# PowerSupplies.net
KiCad netlist of a schematic drawn in Altium Designer
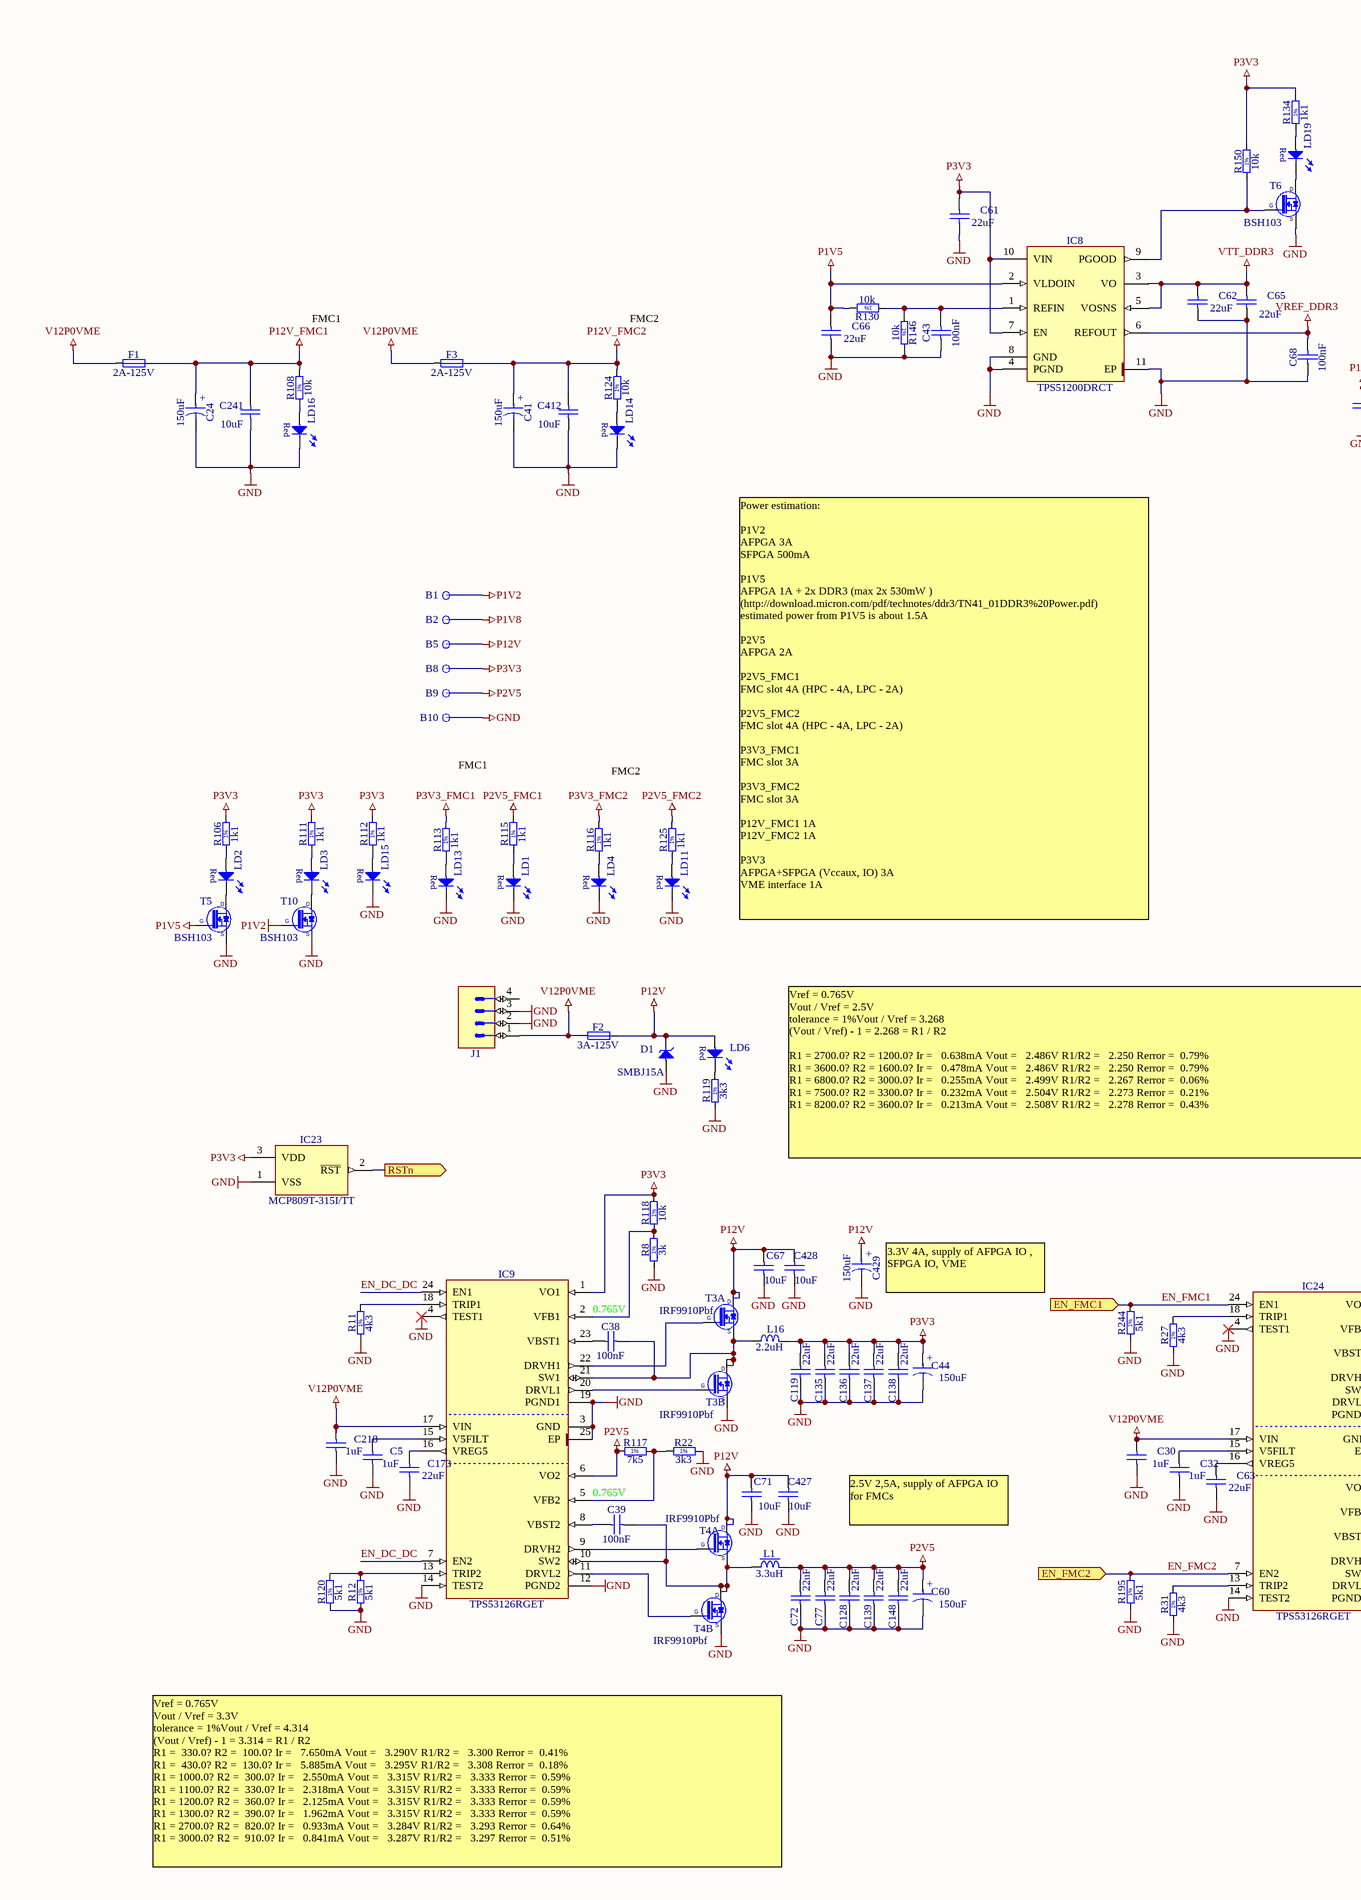
[diagram p0: PowerSupplies.SchDoc, left]
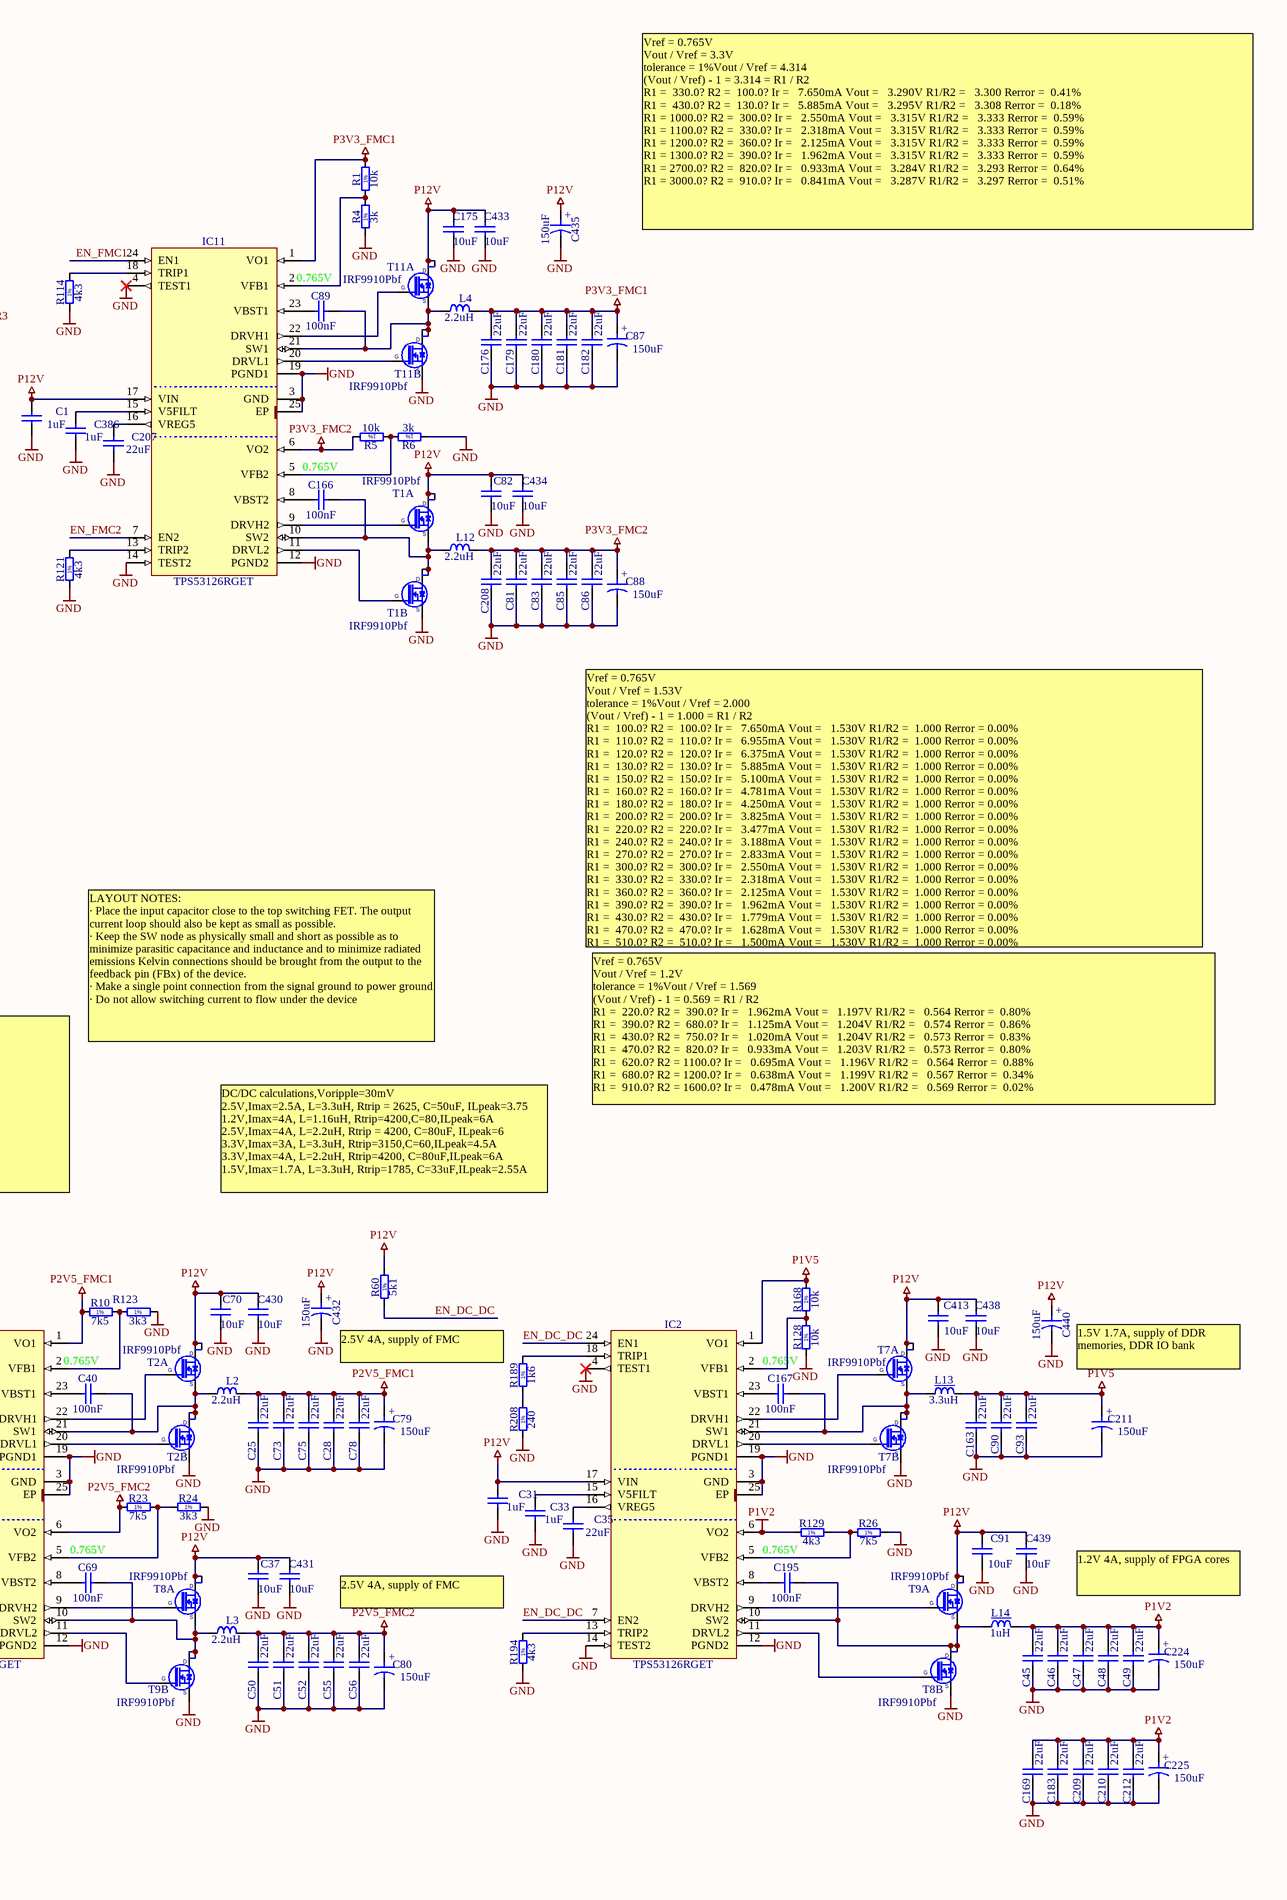
[diagram p1: PowerSupplies.SchDoc, right]

(export (version "E")
  (design (tool "Eeschema 10.0.6"))
  (components
    (comp (ref "B1")
      (value "Plated Hole")
      (footprint "c130h80")
      (description "Single Terminal Socket")
      (fields (field (name "PART NUMBER") "PLATED_HOLE0.8_PAD1.3") (field (name "AUTHOR") "CERN DEM JLC"))
      (libsource (lib "Eletro-mechanical") (part "Single Terminal Socket"))
    )
    (comp (ref "B2")
      (value "Plated Hole")
      (footprint "c130h80")
      (description "Single Terminal Socket")
      (fields (field (name "PART NUMBER") "PLATED_HOLE0.8_PAD1.3") (field (name "AUTHOR") "CERN DEM JLC"))
      (libsource (lib "Eletro-mechanical") (part "Single Terminal Socket"))
    )
    (comp (ref "B5")
      (value "Plated Hole")
      (footprint "c130h80")
      (description "Single Terminal Socket")
      (fields (field (name "PART NUMBER") "PLATED_HOLE0.8_PAD1.3") (field (name "AUTHOR") "CERN DEM JLC"))
      (libsource (lib "Eletro-mechanical") (part "Single Terminal Socket"))
    )
    (comp (ref "B8")
      (value "Plated Hole")
      (footprint "c130h80")
      (description "Single Terminal Socket")
      (fields (field (name "PART NUMBER") "PLATED_HOLE0.8_PAD1.3") (field (name "AUTHOR") "CERN DEM JLC"))
      (libsource (lib "Eletro-mechanical") (part "Single Terminal Socket"))
    )
    (comp (ref "B9")
      (value "Plated Hole")
      (footprint "c130h80")
      (description "Single Terminal Socket")
      (fields (field (name "PART NUMBER") "PLATED_HOLE0.8_PAD1.3") (field (name "AUTHOR") "CERN DEM JLC"))
      (libsource (lib "Eletro-mechanical") (part "Single Terminal Socket"))
    )
    (comp (ref "B10")
      (value "Plated Hole")
      (footprint "c130h80")
      (description "Single Terminal Socket")
      (fields (field (name "PART NUMBER") "PLATED_HOLE0.8_PAD1.3") (field (name "AUTHOR") "CERN DEM JLC"))
      (libsource (lib "Eletro-mechanical") (part "Single Terminal Socket"))
    )
    (comp (ref "C1")
      (value "1uF")
      (footprint "CAPC1608X87N")
      (description "Non-polarised capacitor")
      (fields
        (field (name "PART NUMBER") "CC0603_1UF_16V_10%_X7R")
        (field (name "VOLTAGE") "16V")
        (field (name "AUTHOR") "CERN DEM JLC")
      )
      (libsource (lib "Capacitors") (part "Capacitor - non polarized"))
    )
    (comp (ref "C5")
      (value "1uF")
      (footprint "CAPC1608X87N")
      (description "Non-polarised capacitor")
      (fields
        (field (name "PART NUMBER") "CC0603_1UF_16V_10%_X7R")
        (field (name "VOLTAGE") "16V")
        (field (name "AUTHOR") "CERN DEM JLC")
      )
      (libsource (lib "Capacitors") (part "Capacitor - non polarized"))
    )
    (comp (ref "C24")
      (value "150uF")
      (footprint "CAPPR350-850X700")
      (description "Polarised capacitor")
      (fields
        (field (name "PART NUMBER") "CAER_150UF_6.3V_20%_SANYO_6SEQP150M")
        (field (name "VOLTAGE") "6.3V")
        (field (name "AUTHOR") "CERN DEM JLC")
      )
      (libsource (lib "Capacitors") (part "Capacitor - polarized"))
    )
    (comp (ref "C25")
      (value "22uF")
      (footprint "CAPC3216X180N")
      (description "Non-polarised capacitor")
      (fields
        (field (name "PART NUMBER") "CC1206_22UF_10V_10%_X7R")
        (field (name "VOLTAGE") "10V")
        (field (name "AUTHOR") "CERN DEM JLC")
      )
      (libsource (lib "Capacitors") (part "Capacitor - non polarized"))
    )
    (comp (ref "C28")
      (value "22uF")
      (footprint "CAPC3216X180N")
      (description "Non-polarised capacitor")
      (fields
        (field (name "PART NUMBER") "CC1206_22UF_10V_10%_X7R")
        (field (name "VOLTAGE") "10V")
        (field (name "AUTHOR") "CERN DEM JLC")
      )
      (libsource (lib "Capacitors") (part "Capacitor - non polarized"))
    )
    (comp (ref "C30")
      (value "1uF")
      (footprint "CAPC1608X87N")
      (description "Non-polarised capacitor")
      (fields
        (field (name "PART NUMBER") "CC0603_1UF_16V_10%_X7R")
        (field (name "VOLTAGE") "16V")
        (field (name "AUTHOR") "CERN DEM JLC")
      )
      (libsource (lib "Capacitors") (part "Capacitor - non polarized"))
    )
    (comp (ref "C31")
      (value "1uF")
      (footprint "CAPC1608X87N")
      (description "Non-polarised capacitor")
      (fields
        (field (name "PART NUMBER") "CC0603_1UF_16V_10%_X7R")
        (field (name "VOLTAGE") "16V")
        (field (name "AUTHOR") "CERN DEM JLC")
      )
      (libsource (lib "Capacitors") (part "Capacitor - non polarized"))
    )
    (comp (ref "C32")
      (value "1uF")
      (footprint "CAPC1608X87N")
      (description "Non-polarised capacitor")
      (fields
        (field (name "PART NUMBER") "CC0603_1UF_16V_10%_X7R")
        (field (name "VOLTAGE") "16V")
        (field (name "AUTHOR") "CERN DEM JLC")
      )
      (libsource (lib "Capacitors") (part "Capacitor - non polarized"))
    )
    (comp (ref "C33")
      (value "1uF")
      (footprint "CAPC1608X87N")
      (description "Non-polarised capacitor")
      (fields
        (field (name "PART NUMBER") "CC0603_1UF_16V_10%_X7R")
        (field (name "VOLTAGE") "16V")
        (field (name "AUTHOR") "CERN DEM JLC")
      )
      (libsource (lib "Capacitors") (part "Capacitor - non polarized"))
    )
    (comp (ref "C35")
      (value "22uF")
      (footprint "CAPC3216X180N")
      (description "Non-polarised capacitor")
      (fields
        (field (name "PART NUMBER") "CC1206_22UF_10V_10%_X7R")
        (field (name "VOLTAGE") "10V")
        (field (name "AUTHOR") "CERN DEM JLC")
      )
      (libsource (lib "Capacitors") (part "Capacitor - non polarized"))
    )
    (comp (ref "C37")
      (value "10uF")
      (footprint "CAPC3225X270N")
      (description "Non-polarised capacitor")
      (fields
        (field (name "PART NUMBER") "CC1210_10UF_25V_10%_X7R")
        (field (name "VOLTAGE") "25V")
        (field (name "AUTHOR") "CERN DEM JLC")
      )
      (libsource (lib "Capacitors") (part "Capacitor - non polarized"))
    )
    (comp (ref "C38")
      (value "100nF")
      (footprint "CAPC1005X55N")
      (description "Non-polarised capacitor")
      (fields
        (field (name "PART NUMBER") "CC0402_100NF_16V_10%_X7R")
        (field (name "VOLTAGE") "16V")
        (field (name "AUTHOR") "CERN DEM JLC")
      )
      (libsource (lib "Capacitors") (part "Capacitor - non polarized"))
    )
    (comp (ref "C39")
      (value "100nF")
      (footprint "CAPC1005X55N")
      (description "Non-polarised capacitor")
      (fields
        (field (name "PART NUMBER") "CC0402_100NF_16V_10%_X7R")
        (field (name "VOLTAGE") "16V")
        (field (name "AUTHOR") "CERN DEM JLC")
      )
      (libsource (lib "Capacitors") (part "Capacitor - non polarized"))
    )
    (comp (ref "C40")
      (value "100nF")
      (footprint "CAPC1005X55N")
      (description "Non-polarised capacitor")
      (fields
        (field (name "PART NUMBER") "CC0402_100NF_16V_10%_X7R")
        (field (name "VOLTAGE") "16V")
        (field (name "AUTHOR") "CERN DEM JLC")
      )
      (libsource (lib "Capacitors") (part "Capacitor - non polarized"))
    )
    (comp (ref "C41")
      (value "150uF")
      (footprint "CAPPR350-850X700")
      (description "Polarised capacitor")
      (fields
        (field (name "PART NUMBER") "CAER_150UF_6.3V_20%_SANYO_6SEQP150M")
        (field (name "VOLTAGE") "6.3V")
        (field (name "AUTHOR") "CERN DEM JLC")
      )
      (libsource (lib "Capacitors") (part "Capacitor - polarized"))
    )
    (comp (ref "C43")
      (value "100nF")
      (footprint "CAPC1005X55N")
      (description "Non-polarised capacitor")
      (fields
        (field (name "PART NUMBER") "CC0402_100NF_16V_10%_X7R")
        (field (name "VOLTAGE") "16V")
        (field (name "AUTHOR") "CERN DEM JLC")
      )
      (libsource (lib "Capacitors") (part "Capacitor - non polarized"))
    )
    (comp (ref "C44")
      (value "150uF")
      (footprint "CAPPR350-850X700")
      (description "Polarised capacitor")
      (fields
        (field (name "PART NUMBER") "CAER_150UF_6.3V_20%_SANYO_6SEQP150M")
        (field (name "VOLTAGE") "6.3V")
        (field (name "AUTHOR") "CERN DEM JLC")
      )
      (libsource (lib "Capacitors") (part "Capacitor - polarized"))
    )
    (comp (ref "C45")
      (value "22uF")
      (footprint "CAPC3216X180N")
      (description "Non-polarised capacitor")
      (fields
        (field (name "PART NUMBER") "CC1206_22UF_10V_10%_X7R")
        (field (name "VOLTAGE") "10V")
        (field (name "AUTHOR") "CERN DEM JLC")
      )
      (libsource (lib "Capacitors") (part "Capacitor - non polarized"))
    )
    (comp (ref "C46")
      (value "22uF")
      (footprint "CAPC3216X180N")
      (description "Non-polarised capacitor")
      (fields
        (field (name "PART NUMBER") "CC1206_22UF_10V_10%_X7R")
        (field (name "VOLTAGE") "10V")
        (field (name "AUTHOR") "CERN DEM JLC")
      )
      (libsource (lib "Capacitors") (part "Capacitor - non polarized"))
    )
    (comp (ref "C47")
      (value "22uF")
      (footprint "CAPC3216X180N")
      (description "Non-polarised capacitor")
      (fields
        (field (name "PART NUMBER") "CC1206_22UF_10V_10%_X7R")
        (field (name "VOLTAGE") "10V")
        (field (name "AUTHOR") "CERN DEM JLC")
      )
      (libsource (lib "Capacitors") (part "Capacitor - non polarized"))
    )
    (comp (ref "C48")
      (value "22uF")
      (footprint "CAPC3216X180N")
      (description "Non-polarised capacitor")
      (fields
        (field (name "PART NUMBER") "CC1206_22UF_10V_10%_X7R")
        (field (name "VOLTAGE") "10V")
        (field (name "AUTHOR") "CERN DEM JLC")
      )
      (libsource (lib "Capacitors") (part "Capacitor - non polarized"))
    )
    (comp (ref "C49")
      (value "22uF")
      (footprint "CAPC3216X180N")
      (description "Non-polarised capacitor")
      (fields
        (field (name "PART NUMBER") "CC1206_22UF_10V_10%_X7R")
        (field (name "VOLTAGE") "10V")
        (field (name "AUTHOR") "CERN DEM JLC")
      )
      (libsource (lib "Capacitors") (part "Capacitor - non polarized"))
    )
    (comp (ref "C50")
      (value "22uF")
      (footprint "CAPC3216X180N")
      (description "Non-polarised capacitor")
      (fields
        (field (name "PART NUMBER") "CC1206_22UF_10V_10%_X7R")
        (field (name "VOLTAGE") "10V")
        (field (name "AUTHOR") "CERN DEM JLC")
      )
      (libsource (lib "Capacitors") (part "Capacitor - non polarized"))
    )
    (comp (ref "C51")
      (value "22uF")
      (footprint "CAPC3216X180N")
      (description "Non-polarised capacitor")
      (fields
        (field (name "PART NUMBER") "CC1206_22UF_10V_10%_X7R")
        (field (name "VOLTAGE") "10V")
        (field (name "AUTHOR") "CERN DEM JLC")
      )
      (libsource (lib "Capacitors") (part "Capacitor - non polarized"))
    )
    (comp (ref "C52")
      (value "22uF")
      (footprint "CAPC3216X180N")
      (description "Non-polarised capacitor")
      (fields
        (field (name "PART NUMBER") "CC1206_22UF_10V_10%_X7R")
        (field (name "VOLTAGE") "10V")
        (field (name "AUTHOR") "CERN DEM JLC")
      )
      (libsource (lib "Capacitors") (part "Capacitor - non polarized"))
    )
    (comp (ref "C55")
      (value "22uF")
      (footprint "CAPC3216X180N")
      (description "Non-polarised capacitor")
      (fields
        (field (name "PART NUMBER") "CC1206_22UF_10V_10%_X7R")
        (field (name "VOLTAGE") "10V")
        (field (name "AUTHOR") "CERN DEM JLC")
      )
      (libsource (lib "Capacitors") (part "Capacitor - non polarized"))
    )
    (comp (ref "C56")
      (value "22uF")
      (footprint "CAPC3216X180N")
      (description "Non-polarised capacitor")
      (fields
        (field (name "PART NUMBER") "CC1206_22UF_10V_10%_X7R")
        (field (name "VOLTAGE") "10V")
        (field (name "AUTHOR") "CERN DEM JLC")
      )
      (libsource (lib "Capacitors") (part "Capacitor - non polarized"))
    )
    (comp (ref "C60")
      (value "150uF")
      (footprint "CAPPR350-850X700")
      (description "Polarised capacitor")
      (fields
        (field (name "PART NUMBER") "CAER_150UF_6.3V_20%_SANYO_6SEQP150M")
        (field (name "VOLTAGE") "6.3V")
        (field (name "AUTHOR") "CERN DEM JLC")
      )
      (libsource (lib "Capacitors") (part "Capacitor - polarized"))
    )
    (comp (ref "C61")
      (value "22uF")
      (footprint "CAPC3216X180N")
      (description "Non-polarised capacitor")
      (fields
        (field (name "PART NUMBER") "CC1206_22UF_10V_10%_X7R")
        (field (name "VOLTAGE") "10V")
        (field (name "AUTHOR") "CERN DEM JLC")
      )
      (libsource (lib "Capacitors") (part "Capacitor - non polarized"))
    )
    (comp (ref "C62")
      (value "22uF")
      (footprint "CAPC3216X180N")
      (description "Non-polarised capacitor")
      (fields
        (field (name "PART NUMBER") "CC1206_22UF_10V_10%_X7R")
        (field (name "VOLTAGE") "10V")
        (field (name "AUTHOR") "CERN DEM JLC")
      )
      (libsource (lib "Capacitors") (part "Capacitor - non polarized"))
    )
    (comp (ref "C63")
      (value "22uF")
      (footprint "CAPC3216X180N")
      (description "Non-polarised capacitor")
      (fields
        (field (name "PART NUMBER") "CC1206_22UF_10V_10%_X7R")
        (field (name "VOLTAGE") "10V")
        (field (name "AUTHOR") "CERN DEM JLC")
      )
      (libsource (lib "Capacitors") (part "Capacitor - non polarized"))
    )
    (comp (ref "C65")
      (value "22uF")
      (footprint "CAPC3216X180N")
      (description "Non-polarised capacitor")
      (fields
        (field (name "PART NUMBER") "CC1206_22UF_10V_10%_X7R")
        (field (name "VOLTAGE") "10V")
        (field (name "AUTHOR") "CERN DEM JLC")
      )
      (libsource (lib "Capacitors") (part "Capacitor - non polarized"))
    )
    (comp (ref "C66")
      (value "22uF")
      (footprint "CAPC3216X180N")
      (description "Non-polarised capacitor")
      (fields
        (field (name "PART NUMBER") "CC1206_22UF_10V_10%_X7R")
        (field (name "VOLTAGE") "10V")
        (field (name "AUTHOR") "CERN DEM JLC")
      )
      (libsource (lib "Capacitors") (part "Capacitor - non polarized"))
    )
    (comp (ref "C67")
      (value "10uF")
      (footprint "CAPC3225X270N")
      (description "Non-polarised capacitor")
      (fields
        (field (name "PART NUMBER") "CC1210_10UF_25V_10%_X7R")
        (field (name "VOLTAGE") "25V")
        (field (name "AUTHOR") "CERN DEM JLC")
      )
      (libsource (lib "Capacitors") (part "Capacitor - non polarized"))
    )
    (comp (ref "C68")
      (value "100nF")
      (footprint "CAPC1005X55N")
      (description "Non-polarised capacitor")
      (fields
        (field (name "PART NUMBER") "CC0402_100NF_16V_10%_X7R")
        (field (name "VOLTAGE") "16V")
        (field (name "AUTHOR") "CERN DEM JLC")
      )
      (libsource (lib "Capacitors") (part "Capacitor - non polarized"))
    )
    (comp (ref "C69")
      (value "100nF")
      (footprint "CAPC1005X55N")
      (description "Non-polarised capacitor")
      (fields
        (field (name "PART NUMBER") "CC0402_100NF_16V_10%_X7R")
        (field (name "VOLTAGE") "16V")
        (field (name "AUTHOR") "CERN DEM JLC")
      )
      (libsource (lib "Capacitors") (part "Capacitor - non polarized"))
    )
    (comp (ref "C70")
      (value "10uF")
      (footprint "CAPC3225X270N")
      (description "Non-polarised capacitor")
      (fields
        (field (name "PART NUMBER") "CC1210_10UF_25V_10%_X7R")
        (field (name "VOLTAGE") "25V")
        (field (name "AUTHOR") "CERN DEM JLC")
      )
      (libsource (lib "Capacitors") (part "Capacitor - non polarized"))
    )
    (comp (ref "C71")
      (value "10uF")
      (footprint "CAPC3225X270N")
      (description "Non-polarised capacitor")
      (fields
        (field (name "PART NUMBER") "CC1210_10UF_25V_10%_X7R")
        (field (name "VOLTAGE") "25V")
        (field (name "AUTHOR") "CERN DEM JLC")
      )
      (libsource (lib "Capacitors") (part "Capacitor - non polarized"))
    )
    (comp (ref "C72")
      (value "22uF")
      (footprint "CAPC3216X180N")
      (description "Non-polarised capacitor")
      (fields
        (field (name "PART NUMBER") "CC1206_22UF_10V_10%_X7R")
        (field (name "VOLTAGE") "10V")
        (field (name "AUTHOR") "CERN DEM JLC")
      )
      (libsource (lib "Capacitors") (part "Capacitor - non polarized"))
    )
    (comp (ref "C73")
      (value "22uF")
      (footprint "CAPC3216X180N")
      (description "Non-polarised capacitor")
      (fields
        (field (name "PART NUMBER") "CC1206_22UF_10V_10%_X7R")
        (field (name "VOLTAGE") "10V")
        (field (name "AUTHOR") "CERN DEM JLC")
      )
      (libsource (lib "Capacitors") (part "Capacitor - non polarized"))
    )
    (comp (ref "C75")
      (value "22uF")
      (footprint "CAPC3216X180N")
      (description "Non-polarised capacitor")
      (fields
        (field (name "PART NUMBER") "CC1206_22UF_10V_10%_X7R")
        (field (name "VOLTAGE") "10V")
        (field (name "AUTHOR") "CERN DEM JLC")
      )
      (libsource (lib "Capacitors") (part "Capacitor - non polarized"))
    )
    (comp (ref "C77")
      (value "22uF")
      (footprint "CAPC3216X180N")
      (description "Non-polarised capacitor")
      (fields
        (field (name "PART NUMBER") "CC1206_22UF_10V_10%_X7R")
        (field (name "VOLTAGE") "10V")
        (field (name "AUTHOR") "CERN DEM JLC")
      )
      (libsource (lib "Capacitors") (part "Capacitor - non polarized"))
    )
    (comp (ref "C78")
      (value "22uF")
      (footprint "CAPC3216X180N")
      (description "Non-polarised capacitor")
      (fields
        (field (name "PART NUMBER") "CC1206_22UF_10V_10%_X7R")
        (field (name "VOLTAGE") "10V")
        (field (name "AUTHOR") "CERN DEM JLC")
      )
      (libsource (lib "Capacitors") (part "Capacitor - non polarized"))
    )
    (comp (ref "C79")
      (value "150uF")
      (footprint "CAPPR350-850X700")
      (description "Polarised capacitor")
      (fields
        (field (name "PART NUMBER") "CAER_150UF_6.3V_20%_SANYO_6SEQP150M")
        (field (name "VOLTAGE") "6.3V")
        (field (name "AUTHOR") "CERN DEM JLC")
      )
      (libsource (lib "Capacitors") (part "Capacitor - polarized"))
    )
    (comp (ref "C80")
      (value "150uF")
      (footprint "CAPPR350-850X700")
      (description "Polarised capacitor")
      (fields
        (field (name "PART NUMBER") "CAER_150UF_6.3V_20%_SANYO_6SEQP150M")
        (field (name "VOLTAGE") "6.3V")
        (field (name "AUTHOR") "CERN DEM JLC")
      )
      (libsource (lib "Capacitors") (part "Capacitor - polarized"))
    )
    (comp (ref "C81")
      (value "22uF")
      (footprint "CAPC3216X180N")
      (description "Non-polarised capacitor")
      (fields
        (field (name "PART NUMBER") "CC1206_22UF_10V_10%_X7R")
        (field (name "VOLTAGE") "10V")
        (field (name "AUTHOR") "CERN DEM JLC")
      )
      (libsource (lib "Capacitors") (part "Capacitor - non polarized"))
    )
    (comp (ref "C82")
      (value "10uF")
      (footprint "CAPC3225X270N")
      (description "Non-polarised capacitor")
      (fields
        (field (name "PART NUMBER") "CC1210_10UF_25V_10%_X7R")
        (field (name "VOLTAGE") "25V")
        (field (name "AUTHOR") "CERN DEM JLC")
      )
      (libsource (lib "Capacitors") (part "Capacitor - non polarized"))
    )
    (comp (ref "C83")
      (value "22uF")
      (footprint "CAPC3216X180N")
      (description "Non-polarised capacitor")
      (fields
        (field (name "PART NUMBER") "CC1206_22UF_10V_10%_X7R")
        (field (name "VOLTAGE") "10V")
        (field (name "AUTHOR") "CERN DEM JLC")
      )
      (libsource (lib "Capacitors") (part "Capacitor - non polarized"))
    )
    (comp (ref "C85")
      (value "22uF")
      (footprint "CAPC3216X180N")
      (description "Non-polarised capacitor")
      (fields
        (field (name "PART NUMBER") "CC1206_22UF_10V_10%_X7R")
        (field (name "VOLTAGE") "10V")
        (field (name "AUTHOR") "CERN DEM JLC")
      )
      (libsource (lib "Capacitors") (part "Capacitor - non polarized"))
    )
    (comp (ref "C86")
      (value "22uF")
      (footprint "CAPC3216X180N")
      (description "Non-polarised capacitor")
      (fields
        (field (name "PART NUMBER") "CC1206_22UF_10V_10%_X7R")
        (field (name "VOLTAGE") "10V")
        (field (name "AUTHOR") "CERN DEM JLC")
      )
      (libsource (lib "Capacitors") (part "Capacitor - non polarized"))
    )
    (comp (ref "C87")
      (value "150uF")
      (footprint "CAPPR350-850X700")
      (description "Polarised capacitor")
      (fields
        (field (name "PART NUMBER") "CAER_150UF_6.3V_20%_SANYO_6SEQP150M")
        (field (name "VOLTAGE") "6.3V")
        (field (name "AUTHOR") "CERN DEM JLC")
      )
      (libsource (lib "Capacitors") (part "Capacitor - polarized"))
    )
    (comp (ref "C88")
      (value "150uF")
      (footprint "CAPPR350-850X700")
      (description "Polarised capacitor")
      (fields
        (field (name "PART NUMBER") "CAER_150UF_6.3V_20%_SANYO_6SEQP150M")
        (field (name "VOLTAGE") "6.3V")
        (field (name "AUTHOR") "CERN DEM JLC")
      )
      (libsource (lib "Capacitors") (part "Capacitor - polarized"))
    )
    (comp (ref "C89")
      (value "100nF")
      (footprint "CAPC1005X55N")
      (description "Non-polarised capacitor")
      (fields
        (field (name "PART NUMBER") "CC0402_100NF_16V_10%_X7R")
        (field (name "VOLTAGE") "16V")
        (field (name "AUTHOR") "CERN DEM JLC")
      )
      (libsource (lib "Capacitors") (part "Capacitor - non polarized"))
    )
    (comp (ref "C90")
      (value "22uF")
      (footprint "CAPC3216X180N")
      (description "Non-polarised capacitor")
      (fields
        (field (name "PART NUMBER") "CC1206_22UF_10V_10%_X7R")
        (field (name "VOLTAGE") "10V")
        (field (name "AUTHOR") "CERN DEM JLC")
      )
      (libsource (lib "Capacitors") (part "Capacitor - non polarized"))
    )
    (comp (ref "C91")
      (value "10uF")
      (footprint "CAPC3225X270N")
      (description "Non-polarised capacitor")
      (fields
        (field (name "PART NUMBER") "CC1210_10UF_25V_10%_X7R")
        (field (name "VOLTAGE") "25V")
        (field (name "AUTHOR") "CERN DEM JLC")
      )
      (libsource (lib "Capacitors") (part "Capacitor - non polarized"))
    )
    (comp (ref "C93")
      (value "22uF")
      (footprint "CAPC3216X180N")
      (description "Non-polarised capacitor")
      (fields
        (field (name "PART NUMBER") "CC1206_22UF_10V_10%_X7R")
        (field (name "VOLTAGE") "10V")
        (field (name "AUTHOR") "CERN DEM JLC")
      )
      (libsource (lib "Capacitors") (part "Capacitor - non polarized"))
    )
    (comp (ref "C119")
      (value "22uF")
      (footprint "CAPC3216X180N")
      (description "Non-polarised capacitor")
      (fields
        (field (name "PART NUMBER") "CC1206_22UF_10V_10%_X7R")
        (field (name "VOLTAGE") "10V")
        (field (name "AUTHOR") "CERN DEM JLC")
      )
      (libsource (lib "Capacitors") (part "Capacitor - non polarized"))
    )
    (comp (ref "C128")
      (value "22uF")
      (footprint "CAPC3216X180N")
      (description "Non-polarised capacitor")
      (fields
        (field (name "PART NUMBER") "CC1206_22UF_10V_10%_X7R")
        (field (name "VOLTAGE") "10V")
        (field (name "AUTHOR") "CERN DEM JLC")
      )
      (libsource (lib "Capacitors") (part "Capacitor - non polarized"))
    )
    (comp (ref "C135")
      (value "22uF")
      (footprint "CAPC3216X180N")
      (description "Non-polarised capacitor")
      (fields
        (field (name "PART NUMBER") "CC1206_22UF_10V_10%_X7R")
        (field (name "VOLTAGE") "10V")
        (field (name "AUTHOR") "CERN DEM JLC")
      )
      (libsource (lib "Capacitors") (part "Capacitor - non polarized"))
    )
    (comp (ref "C136")
      (value "22uF")
      (footprint "CAPC3216X180N")
      (description "Non-polarised capacitor")
      (fields
        (field (name "PART NUMBER") "CC1206_22UF_10V_10%_X7R")
        (field (name "VOLTAGE") "10V")
        (field (name "AUTHOR") "CERN DEM JLC")
      )
      (libsource (lib "Capacitors") (part "Capacitor - non polarized"))
    )
    (comp (ref "C137")
      (value "22uF")
      (footprint "CAPC3216X180N")
      (description "Non-polarised capacitor")
      (fields
        (field (name "PART NUMBER") "CC1206_22UF_10V_10%_X7R")
        (field (name "VOLTAGE") "10V")
        (field (name "AUTHOR") "CERN DEM JLC")
      )
      (libsource (lib "Capacitors") (part "Capacitor - non polarized"))
    )
    (comp (ref "C138")
      (value "22uF")
      (footprint "CAPC3216X180N")
      (description "Non-polarised capacitor")
      (fields
        (field (name "PART NUMBER") "CC1206_22UF_10V_10%_X7R")
        (field (name "VOLTAGE") "10V")
        (field (name "AUTHOR") "CERN DEM JLC")
      )
      (libsource (lib "Capacitors") (part "Capacitor - non polarized"))
    )
    (comp (ref "C139")
      (value "22uF")
      (footprint "CAPC3216X180N")
      (description "Non-polarised capacitor")
      (fields
        (field (name "PART NUMBER") "CC1206_22UF_10V_10%_X7R")
        (field (name "VOLTAGE") "10V")
        (field (name "AUTHOR") "CERN DEM JLC")
      )
      (libsource (lib "Capacitors") (part "Capacitor - non polarized"))
    )
    (comp (ref "C148")
      (value "22uF")
      (footprint "CAPC3216X180N")
      (description "Non-polarised capacitor")
      (fields
        (field (name "PART NUMBER") "CC1206_22UF_10V_10%_X7R")
        (field (name "VOLTAGE") "10V")
        (field (name "AUTHOR") "CERN DEM JLC")
      )
      (libsource (lib "Capacitors") (part "Capacitor - non polarized"))
    )
    (comp (ref "C163")
      (value "22uF")
      (footprint "CAPC3216X180N")
      (description "Non-polarised capacitor")
      (fields
        (field (name "PART NUMBER") "CC1206_22UF_10V_10%_X7R")
        (field (name "VOLTAGE") "10V")
        (field (name "AUTHOR") "CERN DEM JLC")
      )
      (libsource (lib "Capacitors") (part "Capacitor - non polarized"))
    )
    (comp (ref "C166")
      (value "100nF")
      (footprint "CAPC1005X55N")
      (description "Non-polarised capacitor")
      (fields
        (field (name "PART NUMBER") "CC0402_100NF_16V_10%_X7R")
        (field (name "VOLTAGE") "16V")
        (field (name "AUTHOR") "CERN DEM JLC")
      )
      (libsource (lib "Capacitors") (part "Capacitor - non polarized"))
    )
    (comp (ref "C167")
      (value "100nF")
      (footprint "CAPC1005X55N")
      (description "Non-polarised capacitor")
      (fields
        (field (name "PART NUMBER") "CC0402_100NF_16V_10%_X7R")
        (field (name "VOLTAGE") "16V")
        (field (name "AUTHOR") "CERN DEM JLC")
      )
      (libsource (lib "Capacitors") (part "Capacitor - non polarized"))
    )
    (comp (ref "C169")
      (value "22uF")
      (footprint "CAPC3216X180N")
      (description "Non-polarised capacitor")
      (fields
        (field (name "PART NUMBER") "CC1206_22UF_10V_10%_X7R")
        (field (name "VOLTAGE") "10V")
        (field (name "AUTHOR") "CERN DEM JLC")
      )
      (libsource (lib "Capacitors") (part "Capacitor - non polarized"))
    )
    (comp (ref "C173")
      (value "22uF")
      (footprint "CAPC3216X180N")
      (description "Non-polarised capacitor")
      (fields
        (field (name "PART NUMBER") "CC1206_22UF_10V_10%_X7R")
        (field (name "VOLTAGE") "10V")
        (field (name "AUTHOR") "CERN DEM JLC")
      )
      (libsource (lib "Capacitors") (part "Capacitor - non polarized"))
    )
    (comp (ref "C175")
      (value "10uF")
      (footprint "CAPC3225X270N")
      (description "Non-polarised capacitor")
      (fields
        (field (name "PART NUMBER") "CC1210_10UF_25V_10%_X7R")
        (field (name "VOLTAGE") "25V")
        (field (name "AUTHOR") "CERN DEM JLC")
      )
      (libsource (lib "Capacitors") (part "Capacitor - non polarized"))
    )
    (comp (ref "C176")
      (value "22uF")
      (footprint "CAPC3216X180N")
      (description "Non-polarised capacitor")
      (fields
        (field (name "PART NUMBER") "CC1206_22UF_10V_10%_X7R")
        (field (name "VOLTAGE") "10V")
        (field (name "AUTHOR") "CERN DEM JLC")
      )
      (libsource (lib "Capacitors") (part "Capacitor - non polarized"))
    )
    (comp (ref "C179")
      (value "22uF")
      (footprint "CAPC3216X180N")
      (description "Non-polarised capacitor")
      (fields
        (field (name "PART NUMBER") "CC1206_22UF_10V_10%_X7R")
        (field (name "VOLTAGE") "10V")
        (field (name "AUTHOR") "CERN DEM JLC")
      )
      (libsource (lib "Capacitors") (part "Capacitor - non polarized"))
    )
    (comp (ref "C180")
      (value "22uF")
      (footprint "CAPC3216X180N")
      (description "Non-polarised capacitor")
      (fields
        (field (name "PART NUMBER") "CC1206_22UF_10V_10%_X7R")
        (field (name "VOLTAGE") "10V")
        (field (name "AUTHOR") "CERN DEM JLC")
      )
      (libsource (lib "Capacitors") (part "Capacitor - non polarized"))
    )
    (comp (ref "C181")
      (value "22uF")
      (footprint "CAPC3216X180N")
      (description "Non-polarised capacitor")
      (fields
        (field (name "PART NUMBER") "CC1206_22UF_10V_10%_X7R")
        (field (name "VOLTAGE") "10V")
        (field (name "AUTHOR") "CERN DEM JLC")
      )
      (libsource (lib "Capacitors") (part "Capacitor - non polarized"))
    )
    (comp (ref "C182")
      (value "22uF")
      (footprint "CAPC3216X180N")
      (description "Non-polarised capacitor")
      (fields
        (field (name "PART NUMBER") "CC1206_22UF_10V_10%_X7R")
        (field (name "VOLTAGE") "10V")
        (field (name "AUTHOR") "CERN DEM JLC")
      )
      (libsource (lib "Capacitors") (part "Capacitor - non polarized"))
    )
    (comp (ref "C183")
      (value "22uF")
      (footprint "CAPC3216X180N")
      (description "Non-polarised capacitor")
      (fields
        (field (name "PART NUMBER") "CC1206_22UF_10V_10%_X7R")
        (field (name "VOLTAGE") "10V")
        (field (name "AUTHOR") "CERN DEM JLC")
      )
      (libsource (lib "Capacitors") (part "Capacitor - non polarized"))
    )
    (comp (ref "C195")
      (value "100nF")
      (footprint "CAPC1005X55N")
      (description "Non-polarised capacitor")
      (fields
        (field (name "PART NUMBER") "CC0402_100NF_16V_10%_X7R")
        (field (name "VOLTAGE") "16V")
        (field (name "AUTHOR") "CERN DEM JLC")
      )
      (libsource (lib "Capacitors") (part "Capacitor - non polarized"))
    )
    (comp (ref "C207")
      (value "22uF")
      (footprint "CAPC3216X180N")
      (description "Non-polarised capacitor")
      (fields
        (field (name "PART NUMBER") "CC1206_22UF_10V_10%_X7R")
        (field (name "VOLTAGE") "10V")
        (field (name "AUTHOR") "CERN DEM JLC")
      )
      (libsource (lib "Capacitors") (part "Capacitor - non polarized"))
    )
    (comp (ref "C208")
      (value "22uF")
      (footprint "CAPC3216X180N")
      (description "Non-polarised capacitor")
      (fields
        (field (name "PART NUMBER") "CC1206_22UF_10V_10%_X7R")
        (field (name "VOLTAGE") "10V")
        (field (name "AUTHOR") "CERN DEM JLC")
      )
      (libsource (lib "Capacitors") (part "Capacitor - non polarized"))
    )
    (comp (ref "C209")
      (value "22uF")
      (footprint "CAPC3216X180N")
      (description "Non-polarised capacitor")
      (fields
        (field (name "PART NUMBER") "CC1206_22UF_10V_10%_X7R")
        (field (name "VOLTAGE") "10V")
        (field (name "AUTHOR") "CERN DEM JLC")
      )
      (libsource (lib "Capacitors") (part "Capacitor - non polarized"))
    )
    (comp (ref "C210")
      (value "22uF")
      (footprint "CAPC3216X180N")
      (description "Non-polarised capacitor")
      (fields
        (field (name "PART NUMBER") "CC1206_22UF_10V_10%_X7R")
        (field (name "VOLTAGE") "10V")
        (field (name "AUTHOR") "CERN DEM JLC")
      )
      (libsource (lib "Capacitors") (part "Capacitor - non polarized"))
    )
    (comp (ref "C211")
      (value "150uF")
      (footprint "CAPPR350-850X700")
      (description "Polarised capacitor")
      (fields
        (field (name "PART NUMBER") "CAER_150UF_6.3V_20%_SANYO_6SEQP150M")
        (field (name "VOLTAGE") "6.3V")
        (field (name "AUTHOR") "CERN DEM JLC")
      )
      (libsource (lib "Capacitors") (part "Capacitor - polarized"))
    )
    (comp (ref "C212")
      (value "22uF")
      (footprint "CAPC3216X180N")
      (description "Non-polarised capacitor")
      (fields
        (field (name "PART NUMBER") "CC1206_22UF_10V_10%_X7R")
        (field (name "VOLTAGE") "10V")
        (field (name "AUTHOR") "CERN DEM JLC")
      )
      (libsource (lib "Capacitors") (part "Capacitor - non polarized"))
    )
    (comp (ref "C218")
      (value "1uF")
      (footprint "CAPC1608X87N")
      (description "Non-polarised capacitor")
      (fields
        (field (name "PART NUMBER") "CC0603_1UF_16V_10%_X7R")
        (field (name "VOLTAGE") "16V")
        (field (name "AUTHOR") "CERN DEM JLC")
      )
      (libsource (lib "Capacitors") (part "Capacitor - non polarized"))
    )
    (comp (ref "C224")
      (value "150uF")
      (footprint "CAPPR350-850X700")
      (description "Polarised capacitor")
      (fields
        (field (name "PART NUMBER") "CAER_150UF_6.3V_20%_SANYO_6SEQP150M")
        (field (name "VOLTAGE") "6.3V")
        (field (name "AUTHOR") "CERN DEM JLC")
      )
      (libsource (lib "Capacitors") (part "Capacitor - polarized"))
    )
    (comp (ref "C225")
      (value "150uF")
      (footprint "CAPPR350-850X700")
      (description "Polarised capacitor")
      (fields
        (field (name "PART NUMBER") "CAER_150UF_6.3V_20%_SANYO_6SEQP150M")
        (field (name "VOLTAGE") "6.3V")
        (field (name "AUTHOR") "CERN DEM JLC")
      )
      (libsource (lib "Capacitors") (part "Capacitor - polarized"))
    )
    (comp (ref "C241")
      (value "10uF")
      (footprint "CAPC3225X270N")
      (description "Non-polarised capacitor")
      (fields
        (field (name "PART NUMBER") "CC1210_10UF_25V_10%_X7R")
        (field (name "VOLTAGE") "25V")
        (field (name "AUTHOR") "CERN DEM JLC")
      )
      (libsource (lib "Capacitors") (part "Capacitor - non polarized"))
    )
    (comp (ref "C386")
      (value "1uF")
      (footprint "CAPC1608X87N")
      (description "Non-polarised capacitor")
      (fields
        (field (name "PART NUMBER") "CC0603_1UF_16V_10%_X7R")
        (field (name "VOLTAGE") "16V")
        (field (name "AUTHOR") "CERN DEM JLC")
      )
      (libsource (lib "Capacitors") (part "Capacitor - non polarized"))
    )
    (comp (ref "C412")
      (value "10uF")
      (footprint "CAPC3225X270N")
      (description "Non-polarised capacitor")
      (fields
        (field (name "PART NUMBER") "CC1210_10UF_25V_10%_X7R")
        (field (name "VOLTAGE") "25V")
        (field (name "AUTHOR") "CERN DEM JLC")
      )
      (libsource (lib "Capacitors") (part "Capacitor - non polarized"))
    )
    (comp (ref "C413")
      (value "10uF")
      (footprint "CAPC3225X270N")
      (description "Non-polarised capacitor")
      (fields
        (field (name "PART NUMBER") "CC1210_10UF_25V_10%_X7R")
        (field (name "VOLTAGE") "25V")
        (field (name "AUTHOR") "CERN DEM JLC")
      )
      (libsource (lib "Capacitors") (part "Capacitor - non polarized"))
    )
    (comp (ref "C427")
      (value "10uF")
      (footprint "CAPC3225X270N")
      (description "Non-polarised capacitor")
      (fields
        (field (name "PART NUMBER") "CC1210_10UF_25V_10%_X7R")
        (field (name "VOLTAGE") "25V")
        (field (name "AUTHOR") "CERN DEM JLC")
      )
      (libsource (lib "Capacitors") (part "Capacitor - non polarized"))
    )
    (comp (ref "C428")
      (value "10uF")
      (footprint "CAPC3225X270N")
      (description "Non-polarised capacitor")
      (fields
        (field (name "PART NUMBER") "CC1210_10UF_25V_10%_X7R")
        (field (name "VOLTAGE") "25V")
        (field (name "AUTHOR") "CERN DEM JLC")
      )
      (libsource (lib "Capacitors") (part "Capacitor - non polarized"))
    )
    (comp (ref "C429")
      (value "150uF")
      (footprint "CAPPR500-1050X800")
      (description "Polarised capacitor")
      (fields
        (field (name "PART NUMBER") "CAER_150UF_16V_20%_SANYO_16SEQP150M")
        (field (name "VOLTAGE") "16V")
        (field (name "AUTHOR") "CERN DEM JLC")
      )
      (libsource (lib "Capacitors") (part "Capacitor - polarized"))
    )
    (comp (ref "C430")
      (value "10uF")
      (footprint "CAPC3225X270N")
      (description "Non-polarised capacitor")
      (fields
        (field (name "PART NUMBER") "CC1210_10UF_25V_10%_X7R")
        (field (name "VOLTAGE") "25V")
        (field (name "AUTHOR") "CERN DEM JLC")
      )
      (libsource (lib "Capacitors") (part "Capacitor - non polarized"))
    )
    (comp (ref "C431")
      (value "10uF")
      (footprint "CAPC3225X270N")
      (description "Non-polarised capacitor")
      (fields
        (field (name "PART NUMBER") "CC1210_10UF_25V_10%_X7R")
        (field (name "VOLTAGE") "25V")
        (field (name "AUTHOR") "CERN DEM JLC")
      )
      (libsource (lib "Capacitors") (part "Capacitor - non polarized"))
    )
    (comp (ref "C432")
      (value "150uF")
      (footprint "CAPPR500-1050X800")
      (description "Polarised capacitor")
      (fields
        (field (name "PART NUMBER") "CAER_150UF_16V_20%_SANYO_16SEQP150M")
        (field (name "VOLTAGE") "16V")
        (field (name "AUTHOR") "CERN DEM JLC")
      )
      (libsource (lib "Capacitors") (part "Capacitor - polarized"))
    )
    (comp (ref "C433")
      (value "10uF")
      (footprint "CAPC3225X270N")
      (description "Non-polarised capacitor")
      (fields
        (field (name "PART NUMBER") "CC1210_10UF_25V_10%_X7R")
        (field (name "VOLTAGE") "25V")
        (field (name "AUTHOR") "CERN DEM JLC")
      )
      (libsource (lib "Capacitors") (part "Capacitor - non polarized"))
    )
    (comp (ref "C434")
      (value "10uF")
      (footprint "CAPC3225X270N")
      (description "Non-polarised capacitor")
      (fields
        (field (name "PART NUMBER") "CC1210_10UF_25V_10%_X7R")
        (field (name "VOLTAGE") "25V")
        (field (name "AUTHOR") "CERN DEM JLC")
      )
      (libsource (lib "Capacitors") (part "Capacitor - non polarized"))
    )
    (comp (ref "C435")
      (value "150uF")
      (footprint "CAPPR500-1050X800")
      (description "Polarised capacitor")
      (fields
        (field (name "PART NUMBER") "CAER_150UF_16V_20%_SANYO_16SEQP150M")
        (field (name "VOLTAGE") "16V")
        (field (name "AUTHOR") "CERN DEM JLC")
      )
      (libsource (lib "Capacitors") (part "Capacitor - polarized"))
    )
    (comp (ref "C438")
      (value "10uF")
      (footprint "CAPC3225X270N")
      (description "Non-polarised capacitor")
      (fields
        (field (name "PART NUMBER") "CC1210_10UF_25V_10%_X7R")
        (field (name "VOLTAGE") "25V")
        (field (name "AUTHOR") "CERN DEM JLC")
      )
      (libsource (lib "Capacitors") (part "Capacitor - non polarized"))
    )
    (comp (ref "C439")
      (value "10uF")
      (footprint "CAPC3225X270N")
      (description "Non-polarised capacitor")
      (fields
        (field (name "PART NUMBER") "CC1210_10UF_25V_10%_X7R")
        (field (name "VOLTAGE") "25V")
        (field (name "AUTHOR") "CERN DEM JLC")
      )
      (libsource (lib "Capacitors") (part "Capacitor - non polarized"))
    )
    (comp (ref "C440")
      (value "150uF")
      (footprint "CAPPR500-1050X800")
      (description "Polarised capacitor")
      (fields
        (field (name "PART NUMBER") "CAER_150UF_16V_20%_SANYO_16SEQP150M")
        (field (name "VOLTAGE") "16V")
        (field (name "AUTHOR") "CERN DEM JLC")
      )
      (libsource (lib "Capacitors") (part "Capacitor - polarized"))
    )
    (comp (ref "D1")
      (value "SMBJ15A")
      (footprint "DIOM5336X265N")
      (description "Zener Diode")
      (fields
        (field (name "VOLTAGE") "15V")
        (field (name "POWER") "600W")
        (field (name "AUTHOR") "CERN DEM JLC")
      )
      (libsource (lib "ICs And Semiconductors") (part "Diode Zener"))
    )
    (comp (ref "F1")
      (value "2A-125V")
      (footprint "FUSE_LITTELFUSE_0154")
      (description "Fuse")
      (fields
        (field (name "PART NUMBER") "FUSE_LITTELFUSE_0154002.DR")
        (field (name "MANUFACTURER") "LITTELFUSE")
        (field (name "AUTHOR") "CERN DEM JMW")
      )
      (libsource (lib "Eletro-mechanical") (part "Fuse"))
    )
    (comp (ref "F2")
      (value "3A-125V")
      (footprint "FUSE_LITTELFUSE_0154")
      (description "Fuse")
      (fields
        (field (name "PART NUMBER") "FUSE_LITTELFUSE_0154003.DR")
        (field (name "MANUFACTURER") "LITTELFUSE")
        (field (name "AUTHOR") "CERN DEM JMW")
      )
      (libsource (lib "Eletro-mechanical") (part "Fuse"))
    )
    (comp (ref "F3")
      (value "2A-125V")
      (footprint "FUSE_LITTELFUSE_0154")
      (description "Fuse")
      (fields
        (field (name "PART NUMBER") "FUSE_LITTELFUSE_0154002.DR")
        (field (name "MANUFACTURER") "LITTELFUSE")
        (field (name "AUTHOR") "CERN DEM JMW")
      )
      (libsource (lib "Eletro-mechanical") (part "Fuse"))
    )
    (comp (ref "IC2")
      (value "TPS53126RGET")
      (footprint "QFN50P400X400X100-25N-S255")
      (description "Dual Synchronous Step-Down Controller For Low Voltage Power Rails")
      (fields (field (name "MANUFACTURER") "TEXAS INSTRUMENTS") (field (name "AUTHOR") "CERN DEM JLC"))
      (libsource (lib "ICs And Semiconductors") (part "TPS53126RGET"))
    )
    (comp (ref "IC8")
      (value "TPS51200DRCT")
      (footprint "SON50P300X300X100-11N-R175X250")
      (description "Sink/Source DDR Termination Regulator")
      (fields (field (name "MANUFACTURER") "TEXAS INSTRUMENTS") (field (name "AUTHOR") "CERN DEM JLC"))
      (libsource (lib "ICs And Semiconductors") (part "TPS51200DRC"))
    )
    (comp (ref "IC9")
      (value "TPS53126RGET")
      (footprint "QFN50P400X400X100-25N-S255")
      (description "Dual Synchronous Step-Down Controller For Low Voltage Power Rails")
      (fields (field (name "MANUFACTURER") "TEXAS INSTRUMENTS") (field (name "AUTHOR") "CERN DEM JLC"))
      (libsource (lib "ICs And Semiconductors") (part "TPS53126RGET"))
    )
    (comp (ref "IC11")
      (value "TPS53126RGET")
      (footprint "QFN50P400X400X100-25N-S255")
      (description "Dual Synchronous Step-Down Controller For Low Voltage Power Rails")
      (fields (field (name "MANUFACTURER") "TEXAS INSTRUMENTS") (field (name "AUTHOR") "CERN DEM JLC"))
      (libsource (lib "ICs And Semiconductors") (part "TPS53126RGET"))
    )
    (comp (ref "IC23")
      (value "MCP809T-315I/TT")
      (footprint "SOT95P237X112-3N")
      (description "3.075V Microcontroller Supervisory Circuit With Push-Pull Output")
      (fields (field (name "MANUFACTURER") "MICROCHIP TECHNOLOGY") (field (name "AUTHOR") "CERN DEM JLC"))
      (libsource (lib "ICs And Semiconductors") (part "MCP809"))
    )
    (comp (ref "IC24")
      (value "TPS53126RGET")
      (footprint "QFN50P400X400X100-25N-S255")
      (description "Dual Synchronous Step-Down Controller For Low Voltage Power Rails")
      (fields (field (name "MANUFACTURER") "TEXAS INSTRUMENTS") (field (name "AUTHOR") "CERN DEM JLC"))
      (libsource (lib "ICs And Semiconductors") (part "TPS53126RGET"))
    )
    (comp (ref "J1")
      (value "Header 4")
      (footprint "TYCO_350211-1")
      (description "Connector 4 Male")
      (fields
        (field (name "PART NUMBER") "TYCO_350211-1")
        (field (name "MANUFACTURER") "TYCO ELECTRONICS")
        (field (name "AUTHOR") "CERN DEM JLC")
      )
      (libsource (lib "Connectors") (part "Connector 4 Male"))
    )
    (comp (ref "L1")
      (value "3.3uH")
      (footprint "IND_COILCRAFT_DO3316")
      (description "Inductor With Magnetic core")
      (fields
        (field (name "PART NUMBER") "IND_3.3UH_20%_COILCRAFT_DO3316P-332MLD")
        (field (name "POWER") "5.4A")
        (field (name "AUTHOR") "CERN DEM JLC")
      )
      (libsource (lib "Inductors & Transformers") (part "Inductor With Magnetic core"))
    )
    (comp (ref "L2")
      (value "2.2uH")
      (footprint "IND_BOURNS_SRR1260")
      (description "Inductor")
      (fields
        (field (name "PART NUMBER") "IND_2.2UH_30%_BOURNS_SRR1260")
        (field (name "POWER") "8.2A")
        (field (name "AUTHOR") "CERN DEM JLC")
      )
      (libsource (lib "Inductors & Transformers") (part "Inductor"))
    )
    (comp (ref "L3")
      (value "2.2uH")
      (footprint "IND_BOURNS_SRR1260")
      (description "Inductor")
      (fields
        (field (name "PART NUMBER") "IND_2.2UH_30%_BOURNS_SRR1260")
        (field (name "POWER") "8.2A")
        (field (name "AUTHOR") "CERN DEM JLC")
      )
      (libsource (lib "Inductors & Transformers") (part "Inductor"))
    )
    (comp (ref "L4")
      (value "2.2uH")
      (footprint "IND_BOURNS_SRR1260")
      (description "Inductor")
      (fields
        (field (name "PART NUMBER") "IND_2.2UH_30%_BOURNS_SRR1260")
        (field (name "POWER") "8.2A")
        (field (name "AUTHOR") "CERN DEM JLC")
      )
      (libsource (lib "Inductors & Transformers") (part "Inductor"))
    )
    (comp (ref "L12")
      (value "2.2uH")
      (footprint "IND_BOURNS_SRR1260")
      (description "Inductor")
      (fields
        (field (name "PART NUMBER") "IND_2.2UH_30%_BOURNS_SRR1260")
        (field (name "POWER") "8.2A")
        (field (name "AUTHOR") "CERN DEM JLC")
      )
      (libsource (lib "Inductors & Transformers") (part "Inductor"))
    )
    (comp (ref "L13")
      (value "3.3uH")
      (footprint "IND_COILCRAFT_DO3316")
      (description "Inductor With Magnetic core")
      (fields
        (field (name "PART NUMBER") "IND_3.3UH_20%_COILCRAFT_DO3316P-332MLD")
        (field (name "POWER") "5.4A")
        (field (name "AUTHOR") "CERN DEM JLC")
      )
      (libsource (lib "Inductors & Transformers") (part "Inductor With Magnetic core"))
    )
    (comp (ref "L14")
      (value "1uH")
      (footprint "IND_COILCRAFT_DO3316")
      (description "Inductor With Magnetic core")
      (fields
        (field (name "PART NUMBER") "IND_1UH_20%_COILCRAFT_DO3316P-102MLD")
        (field (name "POWER") "6.8A")
        (field (name "AUTHOR") "CERN DEM JLC")
      )
      (libsource (lib "Inductors & Transformers") (part "Inductor With Magnetic core"))
    )
    (comp (ref "L16")
      (value "2.2uH")
      (footprint "IND_BOURNS_SRR1260")
      (description "Inductor")
      (fields
        (field (name "PART NUMBER") "IND_2.2UH_30%_BOURNS_SRR1260")
        (field (name "POWER") "8.2A")
        (field (name "AUTHOR") "CERN DEM JLC")
      )
      (libsource (lib "Inductors & Transformers") (part "Inductor"))
    )
    (comp (ref "LD1")
      (value "Red")
      (footprint "LEDC1608X80N_RED")
      (description "LED Red 1C 2A")
      (fields
        (field (name "PART NUMBER") "LED_ROHM_SML-311UTT86K")
        (field (name "MANUFACTURER") "ROHM")
        (field (name "AUTHOR") "CERN DEM JLC")
      )
      (libsource (lib "ICs And Semiconductors") (part "LED Red 1C 2A"))
    )
    (comp (ref "LD2")
      (value "Red")
      (footprint "LEDC1608X80N_RED")
      (description "LED Red 1C 2A")
      (fields
        (field (name "PART NUMBER") "LED_ROHM_SML-311UTT86K")
        (field (name "MANUFACTURER") "ROHM")
        (field (name "AUTHOR") "CERN DEM JLC")
      )
      (libsource (lib "ICs And Semiconductors") (part "LED Red 1C 2A"))
    )
    (comp (ref "LD3")
      (value "Red")
      (footprint "LEDC1608X80N_RED")
      (description "LED Red 1C 2A")
      (fields
        (field (name "PART NUMBER") "LED_ROHM_SML-311UTT86K")
        (field (name "MANUFACTURER") "ROHM")
        (field (name "AUTHOR") "CERN DEM JLC")
      )
      (libsource (lib "ICs And Semiconductors") (part "LED Red 1C 2A"))
    )
    (comp (ref "LD4")
      (value "Red")
      (footprint "LEDC1608X80N_RED")
      (description "LED Red 1C 2A")
      (fields
        (field (name "PART NUMBER") "LED_ROHM_SML-311UTT86K")
        (field (name "MANUFACTURER") "ROHM")
        (field (name "AUTHOR") "CERN DEM JLC")
      )
      (libsource (lib "ICs And Semiconductors") (part "LED Red 1C 2A"))
    )
    (comp (ref "LD6")
      (value "Red")
      (footprint "LEDC1608X80N_RED")
      (description "LED Red 1C 2A")
      (fields
        (field (name "PART NUMBER") "LED_ROHM_SML-311UTT86K")
        (field (name "MANUFACTURER") "ROHM")
        (field (name "AUTHOR") "CERN DEM JLC")
      )
      (libsource (lib "ICs And Semiconductors") (part "LED Red 1C 2A"))
    )
    (comp (ref "LD11")
      (value "Red")
      (footprint "LEDC1608X80N_RED")
      (description "LED Red 1C 2A")
      (fields
        (field (name "PART NUMBER") "LED_ROHM_SML-311UTT86K")
        (field (name "MANUFACTURER") "ROHM")
        (field (name "AUTHOR") "CERN DEM JLC")
      )
      (libsource (lib "ICs And Semiconductors") (part "LED Red 1C 2A"))
    )
    (comp (ref "LD13")
      (value "Red")
      (footprint "LEDC1608X80N_RED")
      (description "LED Red 1C 2A")
      (fields
        (field (name "PART NUMBER") "LED_ROHM_SML-311UTT86K")
        (field (name "MANUFACTURER") "ROHM")
        (field (name "AUTHOR") "CERN DEM JLC")
      )
      (libsource (lib "ICs And Semiconductors") (part "LED Red 1C 2A"))
    )
    (comp (ref "LD14")
      (value "Red")
      (footprint "LEDC1608X80N_RED")
      (description "LED Red 1C 2A")
      (fields
        (field (name "PART NUMBER") "LED_ROHM_SML-311UTT86K")
        (field (name "MANUFACTURER") "ROHM")
        (field (name "AUTHOR") "CERN DEM JLC")
      )
      (libsource (lib "ICs And Semiconductors") (part "LED Red 1C 2A"))
    )
    (comp (ref "LD15")
      (value "Red")
      (footprint "LEDC1608X80N_RED")
      (description "LED Red 1C 2A")
      (fields
        (field (name "PART NUMBER") "LED_ROHM_SML-311UTT86K")
        (field (name "MANUFACTURER") "ROHM")
        (field (name "AUTHOR") "CERN DEM JLC")
      )
      (libsource (lib "ICs And Semiconductors") (part "LED Red 1C 2A"))
    )
    (comp (ref "LD16")
      (value "Red")
      (footprint "LEDC1608X80N_RED")
      (description "LED Red 1C 2A")
      (fields
        (field (name "PART NUMBER") "LED_ROHM_SML-311UTT86K")
        (field (name "MANUFACTURER") "ROHM")
        (field (name "AUTHOR") "CERN DEM JLC")
      )
      (libsource (lib "ICs And Semiconductors") (part "LED Red 1C 2A"))
    )
    (comp (ref "LD19")
      (value "Red")
      (footprint "LEDC1608X80N_RED")
      (description "LED Red 1C 2A")
      (fields
        (field (name "PART NUMBER") "LED_ROHM_SML-311UTT86K")
        (field (name "MANUFACTURER") "ROHM")
        (field (name "AUTHOR") "CERN DEM JLC")
      )
      (libsource (lib "ICs And Semiconductors") (part "LED Red 1C 2A"))
    )
    (comp (ref "R1")
      (value "10k")
      (footprint "RESC1608X55N")
      (description "Resistor - 1%")
      (fields
        (field (name "PART NUMBER") "R0603_10K_1%_0.1W_100PPM")
        (field (name "POWER") "0.1W")
        (field (name "AUTHOR") "CERN DEM JLC")
      )
      (libsource (lib "Resistors") (part "Resistor - 1%"))
    )
    (comp (ref "R4")
      (value "3k")
      (footprint "RESC1608X55N")
      (description "Resistor - 1%")
      (fields
        (field (name "PART NUMBER") "R0603_3K_1%_0.1W_100PPM")
        (field (name "POWER") "0.1W")
        (field (name "AUTHOR") "CERN DEM JLC")
      )
      (libsource (lib "Resistors") (part "Resistor - 1%"))
    )
    (comp (ref "R5")
      (value "10k")
      (footprint "RESC1608X55N")
      (description "Resistor - 1%")
      (fields
        (field (name "PART NUMBER") "R0603_10K_1%_0.1W_100PPM")
        (field (name "POWER") "0.1W")
        (field (name "AUTHOR") "CERN DEM JLC")
      )
      (libsource (lib "Resistors") (part "Resistor - 1%"))
    )
    (comp (ref "R6")
      (value "3k")
      (footprint "RESC1608X55N")
      (description "Resistor - 1%")
      (fields
        (field (name "PART NUMBER") "R0603_3K_1%_0.1W_100PPM")
        (field (name "POWER") "0.1W")
        (field (name "AUTHOR") "CERN DEM JLC")
      )
      (libsource (lib "Resistors") (part "Resistor - 1%"))
    )
    (comp (ref "R8")
      (value "3k")
      (footprint "RESC1608X55N")
      (description "Resistor - 1%")
      (fields
        (field (name "PART NUMBER") "R0603_3K_1%_0.1W_100PPM")
        (field (name "POWER") "0.1W")
        (field (name "AUTHOR") "CERN DEM JLC")
      )
      (libsource (lib "Resistors") (part "Resistor - 1%"))
    )
    (comp (ref "R10")
      (value "7k5")
      (footprint "RESC1608X55N")
      (description "Resistor - 1%")
      (fields
        (field (name "PART NUMBER") "R0603_7K5_1%_0.1W_100PPM")
        (field (name "POWER") "0.1W")
        (field (name "AUTHOR") "CERN DEM JLC")
      )
      (libsource (lib "Resistors") (part "Resistor - 1%"))
    )
    (comp (ref "R11")
      (value "4k3")
      (footprint "RESC1608X55N")
      (description "Resistor - 1%")
      (fields
        (field (name "PART NUMBER") "R0603_4K3_1%_0.1W_100PPM")
        (field (name "POWER") "0.1W")
        (field (name "AUTHOR") "CERN DEM JLC")
      )
      (libsource (lib "Resistors") (part "Resistor - 1%"))
    )
    (comp (ref "R12")
      (value "5k1")
      (footprint "RESC1608X55N")
      (description "Resistor - 1%")
      (fields
        (field (name "PART NUMBER") "R0603_5K1_1%_0.1W_100PPM")
        (field (name "POWER") "0.1W")
        (field (name "AUTHOR") "CERN DEM JLC")
      )
      (libsource (lib "Resistors") (part "Resistor - 1%"))
    )
    (comp (ref "R22")
      (value "3k3")
      (footprint "RESC1608X55N")
      (description "Resistor - 1%")
      (fields
        (field (name "PART NUMBER") "R0603_3K3_1%_0.1W_100PPM")
        (field (name "POWER") "0.1W")
        (field (name "AUTHOR") "CERN DEM JLC")
      )
      (libsource (lib "Resistors") (part "Resistor - 1%"))
    )
    (comp (ref "R23")
      (value "7k5")
      (footprint "RESC1608X55N")
      (description "Resistor - 1%")
      (fields
        (field (name "PART NUMBER") "R0603_7K5_1%_0.1W_100PPM")
        (field (name "POWER") "0.1W")
        (field (name "AUTHOR") "CERN DEM JLC")
      )
      (libsource (lib "Resistors") (part "Resistor - 1%"))
    )
    (comp (ref "R24")
      (value "3k3")
      (footprint "RESC1608X55N")
      (description "Resistor - 1%")
      (fields
        (field (name "PART NUMBER") "R0603_3K3_1%_0.1W_100PPM")
        (field (name "POWER") "0.1W")
        (field (name "AUTHOR") "CERN DEM JLC")
      )
      (libsource (lib "Resistors") (part "Resistor - 1%"))
    )
    (comp (ref "R26")
      (value "7k5")
      (footprint "RESC1608X55N")
      (description "Resistor - 1%")
      (fields
        (field (name "PART NUMBER") "R0603_7K5_1%_0.1W_100PPM")
        (field (name "POWER") "0.1W")
        (field (name "AUTHOR") "CERN DEM JLC")
      )
      (libsource (lib "Resistors") (part "Resistor - 1%"))
    )
    (comp (ref "R27")
      (value "4k3")
      (footprint "RESC1608X55N")
      (description "Resistor - 1%")
      (fields
        (field (name "PART NUMBER") "R0603_4K3_1%_0.1W_100PPM")
        (field (name "POWER") "0.1W")
        (field (name "AUTHOR") "CERN DEM JLC")
      )
      (libsource (lib "Resistors") (part "Resistor - 1%"))
    )
    (comp (ref "R31")
      (value "4k3")
      (footprint "RESC1608X55N")
      (description "Resistor - 1%")
      (fields
        (field (name "PART NUMBER") "R0603_4K3_1%_0.1W_100PPM")
        (field (name "POWER") "0.1W")
        (field (name "AUTHOR") "CERN DEM JLC")
      )
      (libsource (lib "Resistors") (part "Resistor - 1%"))
    )
    (comp (ref "R60")
      (value "5k1")
      (footprint "RESC1608X55N")
      (description "Resistor - 1%")
      (fields
        (field (name "PART NUMBER") "R0603_5K1_1%_0.1W_100PPM")
        (field (name "POWER") "0.1W")
        (field (name "AUTHOR") "CERN DEM JLC")
      )
      (libsource (lib "Resistors") (part "Resistor - 1%"))
    )
    (comp (ref "R106")
      (value "1k1")
      (footprint "RESC1608X55N")
      (description "Resistor - 1%")
      (fields
        (field (name "PART NUMBER") "R0603_1K1_1%_0.1W_100PPM")
        (field (name "POWER") "0.1W")
        (field (name "AUTHOR") "CERN DEM JLC")
      )
      (libsource (lib "Resistors") (part "Resistor - 1%"))
    )
    (comp (ref "R108")
      (value "10k")
      (footprint "RESC1608X55N")
      (description "Resistor - 1%")
      (fields
        (field (name "PART NUMBER") "R0603_10K_1%_0.1W_100PPM")
        (field (name "POWER") "0.1W")
        (field (name "AUTHOR") "CERN DEM JLC")
      )
      (libsource (lib "Resistors") (part "Resistor - 1%"))
    )
    (comp (ref "R111")
      (value "1k1")
      (footprint "RESC1608X55N")
      (description "Resistor - 1%")
      (fields
        (field (name "PART NUMBER") "R0603_1K1_1%_0.1W_100PPM")
        (field (name "POWER") "0.1W")
        (field (name "AUTHOR") "CERN DEM JLC")
      )
      (libsource (lib "Resistors") (part "Resistor - 1%"))
    )
    (comp (ref "R112")
      (value "1k1")
      (footprint "RESC1608X55N")
      (description "Resistor - 1%")
      (fields
        (field (name "PART NUMBER") "R0603_1K1_1%_0.1W_100PPM")
        (field (name "POWER") "0.1W")
        (field (name "AUTHOR") "CERN DEM JLC")
      )
      (libsource (lib "Resistors") (part "Resistor - 1%"))
    )
    (comp (ref "R113")
      (value "1k1")
      (footprint "RESC1608X55N")
      (description "Resistor - 1%")
      (fields
        (field (name "PART NUMBER") "R0603_1K1_1%_0.1W_100PPM")
        (field (name "POWER") "0.1W")
        (field (name "AUTHOR") "CERN DEM JLC")
      )
      (libsource (lib "Resistors") (part "Resistor - 1%"))
    )
    (comp (ref "R114")
      (value "4k3")
      (footprint "RESC1608X55N")
      (description "Resistor - 1%")
      (fields
        (field (name "PART NUMBER") "R0603_4K3_1%_0.1W_100PPM")
        (field (name "POWER") "0.1W")
        (field (name "AUTHOR") "CERN DEM JLC")
      )
      (libsource (lib "Resistors") (part "Resistor - 1%"))
    )
    (comp (ref "R115")
      (value "1k1")
      (footprint "RESC1608X55N")
      (description "Resistor - 1%")
      (fields
        (field (name "PART NUMBER") "R0603_1K1_1%_0.1W_100PPM")
        (field (name "POWER") "0.1W")
        (field (name "AUTHOR") "CERN DEM JLC")
      )
      (libsource (lib "Resistors") (part "Resistor - 1%"))
    )
    (comp (ref "R116")
      (value "1k1")
      (footprint "RESC1608X55N")
      (description "Resistor - 1%")
      (fields
        (field (name "PART NUMBER") "R0603_1K1_1%_0.1W_100PPM")
        (field (name "POWER") "0.1W")
        (field (name "AUTHOR") "CERN DEM JLC")
      )
      (libsource (lib "Resistors") (part "Resistor - 1%"))
    )
    (comp (ref "R117")
      (value "7k5")
      (footprint "RESC1608X55N")
      (description "Resistor - 1%")
      (fields
        (field (name "PART NUMBER") "R0603_7K5_1%_0.1W_100PPM")
        (field (name "POWER") "0.1W")
        (field (name "AUTHOR") "CERN DEM JLC")
      )
      (libsource (lib "Resistors") (part "Resistor - 1%"))
    )
    (comp (ref "R118")
      (value "10k")
      (footprint "RESC1608X55N")
      (description "Resistor - 1%")
      (fields
        (field (name "PART NUMBER") "R0603_10K_1%_0.1W_100PPM")
        (field (name "POWER") "0.1W")
        (field (name "AUTHOR") "CERN DEM JLC")
      )
      (libsource (lib "Resistors") (part "Resistor - 1%"))
    )
    (comp (ref "R119")
      (value "3k3")
      (footprint "RESC1608X55N")
      (description "Resistor - 1%")
      (fields
        (field (name "PART NUMBER") "R0603_3K3_1%_0.1W_100PPM")
        (field (name "POWER") "0.1W")
        (field (name "AUTHOR") "CERN DEM JLC")
      )
      (libsource (lib "Resistors") (part "Resistor - 1%"))
    )
    (comp (ref "R120")
      (value "5k1")
      (footprint "RESC1608X55N")
      (description "Resistor - 1%")
      (fields
        (field (name "PART NUMBER") "R0603_5K1_1%_0.1W_100PPM")
        (field (name "POWER") "0.1W")
        (field (name "AUTHOR") "CERN DEM JLC")
      )
      (libsource (lib "Resistors") (part "Resistor - 1%"))
    )
    (comp (ref "R121")
      (value "4k3")
      (footprint "RESC1608X55N")
      (description "Resistor - 1%")
      (fields
        (field (name "PART NUMBER") "R0603_4K3_1%_0.1W_100PPM")
        (field (name "POWER") "0.1W")
        (field (name "AUTHOR") "CERN DEM JLC")
      )
      (libsource (lib "Resistors") (part "Resistor - 1%"))
    )
    (comp (ref "R123")
      (value "3k3")
      (footprint "RESC1608X55N")
      (description "Resistor - 1%")
      (fields
        (field (name "PART NUMBER") "R0603_3K3_1%_0.1W_100PPM")
        (field (name "POWER") "0.1W")
        (field (name "AUTHOR") "CERN DEM JLC")
      )
      (libsource (lib "Resistors") (part "Resistor - 1%"))
    )
    (comp (ref "R124")
      (value "10k")
      (footprint "RESC1608X55N")
      (description "Resistor - 1%")
      (fields
        (field (name "PART NUMBER") "R0603_10K_1%_0.1W_100PPM")
        (field (name "POWER") "0.1W")
        (field (name "AUTHOR") "CERN DEM JLC")
      )
      (libsource (lib "Resistors") (part "Resistor - 1%"))
    )
    (comp (ref "R125")
      (value "1k1")
      (footprint "RESC1608X55N")
      (description "Resistor - 1%")
      (fields
        (field (name "PART NUMBER") "R0603_1K1_1%_0.1W_100PPM")
        (field (name "POWER") "0.1W")
        (field (name "AUTHOR") "CERN DEM JLC")
      )
      (libsource (lib "Resistors") (part "Resistor - 1%"))
    )
    (comp (ref "R128")
      (value "10k")
      (footprint "RESC1608X55N")
      (description "Resistor - 1%")
      (fields
        (field (name "PART NUMBER") "R0603_10K_1%_0.1W_100PPM")
        (field (name "POWER") "0.1W")
        (field (name "AUTHOR") "CERN DEM JLC")
      )
      (libsource (lib "Resistors") (part "Resistor - 1%"))
    )
    (comp (ref "R129")
      (value "4k3")
      (footprint "RESC1608X55N")
      (description "Resistor - 1%")
      (fields
        (field (name "PART NUMBER") "R0603_4K3_1%_0.1W_100PPM")
        (field (name "POWER") "0.1W")
        (field (name "AUTHOR") "CERN DEM JLC")
      )
      (libsource (lib "Resistors") (part "Resistor - 1%"))
    )
    (comp (ref "R130")
      (value "10k")
      (footprint "RESC1608X55N")
      (description "Resistor - 1%")
      (fields
        (field (name "PART NUMBER") "R0603_10K_1%_0.1W_100PPM")
        (field (name "POWER") "0.1W")
        (field (name "AUTHOR") "CERN DEM JLC")
      )
      (libsource (lib "Resistors") (part "Resistor - 1%"))
    )
    (comp (ref "R134")
      (value "1k1")
      (footprint "RESC1608X55N")
      (description "Resistor - 1%")
      (fields
        (field (name "PART NUMBER") "R0603_1K1_1%_0.1W_100PPM")
        (field (name "POWER") "0.1W")
        (field (name "AUTHOR") "CERN DEM JLC")
      )
      (libsource (lib "Resistors") (part "Resistor - 1%"))
    )
    (comp (ref "R146")
      (value "10k")
      (footprint "RESC1608X55N")
      (description "Resistor - 1%")
      (fields
        (field (name "PART NUMBER") "R0603_10K_1%_0.1W_100PPM")
        (field (name "POWER") "0.1W")
        (field (name "AUTHOR") "CERN DEM JLC")
      )
      (libsource (lib "Resistors") (part "Resistor - 1%"))
    )
    (comp (ref "R150")
      (value "10k")
      (footprint "RESC1608X55N")
      (description "Resistor - 1%")
      (fields
        (field (name "PART NUMBER") "R0603_10K_1%_0.1W_100PPM")
        (field (name "POWER") "0.1W")
        (field (name "AUTHOR") "CERN DEM JLC")
      )
      (libsource (lib "Resistors") (part "Resistor - 1%"))
    )
    (comp (ref "R168")
      (value "10k")
      (footprint "RESC1608X55N")
      (description "Resistor - 1%")
      (fields
        (field (name "PART NUMBER") "R0603_10K_1%_0.1W_100PPM")
        (field (name "POWER") "0.1W")
        (field (name "AUTHOR") "CERN DEM JLC")
      )
      (libsource (lib "Resistors") (part "Resistor - 1%"))
    )
    (comp (ref "R189")
      (value "1k6")
      (footprint "RESC1608X55N")
      (description "Resistor - 1%")
      (fields
        (field (name "PART NUMBER") "R0603_1K6_1%_0.1W_100PPM")
        (field (name "POWER") "0.1W")
        (field (name "AUTHOR") "CERN DEM JLC")
      )
      (libsource (lib "Resistors") (part "Resistor - 1%"))
    )
    (comp (ref "R194")
      (value "4k3")
      (footprint "RESC1608X55N")
      (description "Resistor - 1%")
      (fields
        (field (name "PART NUMBER") "R0603_4K3_1%_0.1W_100PPM")
        (field (name "POWER") "0.1W")
        (field (name "AUTHOR") "CERN DEM JLC")
      )
      (libsource (lib "Resistors") (part "Resistor - 1%"))
    )
    (comp (ref "R195")
      (value "5k1")
      (footprint "RESC1608X55N")
      (description "Resistor - 1%")
      (fields
        (field (name "PART NUMBER") "R0603_5K1_1%_0.1W_100PPM")
        (field (name "POWER") "0.1W")
        (field (name "AUTHOR") "CERN DEM JLC")
      )
      (libsource (lib "Resistors") (part "Resistor - 1%"))
    )
    (comp (ref "R208")
      (value "240")
      (footprint "RESC1608X55N")
      (description "Resistor - 1%")
      (fields
        (field (name "PART NUMBER") "R0603_240R_1%_0.1W_100PPM")
        (field (name "POWER") "0.1W")
        (field (name "AUTHOR") "CERN DEM JLC")
      )
      (libsource (lib "Resistors") (part "Resistor - 1%"))
    )
    (comp (ref "R244")
      (value "5k1")
      (footprint "RESC1608X55N")
      (description "Resistor - 1%")
      (fields
        (field (name "PART NUMBER") "R0603_5K1_1%_0.1W_100PPM")
        (field (name "POWER") "0.1W")
        (field (name "AUTHOR") "CERN DEM JLC")
      )
      (libsource (lib "Resistors") (part "Resistor - 1%"))
    )
    (comp (ref "T1")
      (value "IRF9910Pbf")
      (footprint "SOIC127P600X175-8N")
      (description "Dual SO-8 MOSFET For POL Cconverter")
      (fields (field (name "MANUFACTURER") "INTERNATIONAL RECTIFIER") (field (name "AUTHOR") "CERN DEM JLC"))
      (libsource (lib "ICs And Semiconductors") (part "IRF9910"))
    )
    (comp (ref "T2")
      (value "IRF9910Pbf")
      (footprint "SOIC127P600X175-8N")
      (description "Dual SO-8 MOSFET For POL Cconverter")
      (fields (field (name "MANUFACTURER") "INTERNATIONAL RECTIFIER") (field (name "AUTHOR") "CERN DEM JLC"))
      (libsource (lib "ICs And Semiconductors") (part "IRF9910"))
    )
    (comp (ref "T3")
      (value "IRF9910Pbf")
      (footprint "SOIC127P600X175-8N")
      (description "Dual SO-8 MOSFET For POL Cconverter")
      (fields (field (name "MANUFACTURER") "INTERNATIONAL RECTIFIER") (field (name "AUTHOR") "CERN DEM JLC"))
      (libsource (lib "ICs And Semiconductors") (part "IRF9910"))
    )
    (comp (ref "T4")
      (value "IRF9910Pbf")
      (footprint "SOIC127P600X175-8N")
      (description "Dual SO-8 MOSFET For POL Cconverter")
      (fields (field (name "MANUFACTURER") "INTERNATIONAL RECTIFIER") (field (name "AUTHOR") "CERN DEM JLC"))
      (libsource (lib "ICs And Semiconductors") (part "IRF9910"))
    )
    (comp (ref "T5")
      (value "BSH103")
      (footprint "SOT95P230X110-3N")
      (description "N-CHANNEL MOSFET WITH DIODE")
      (fields (field (name "MANUFACTURER") "NXP SEMICONDUCTORS") (field (name "AUTHOR") "CERN DEM JLC"))
      (libsource (lib "ICs And Semiconductors") (part "N-MOSFET-D 1G 2S 3D"))
    )
    (comp (ref "T6")
      (value "BSH103")
      (footprint "SOT95P230X110-3N")
      (description "N-CHANNEL MOSFET WITH DIODE")
      (fields (field (name "MANUFACTURER") "NXP SEMICONDUCTORS") (field (name "AUTHOR") "CERN DEM JLC"))
      (libsource (lib "ICs And Semiconductors") (part "N-MOSFET-D 1G 2S 3D"))
    )
    (comp (ref "T7")
      (value "IRF9910Pbf")
      (footprint "SOIC127P600X175-8N")
      (description "Dual SO-8 MOSFET For POL Cconverter")
      (fields (field (name "MANUFACTURER") "INTERNATIONAL RECTIFIER") (field (name "AUTHOR") "CERN DEM JLC"))
      (libsource (lib "ICs And Semiconductors") (part "IRF9910"))
    )
    (comp (ref "T8")
      (value "IRF9910Pbf")
      (footprint "SOIC127P600X175-8N")
      (description "Dual SO-8 MOSFET For POL Cconverter")
      (fields (field (name "MANUFACTURER") "INTERNATIONAL RECTIFIER") (field (name "AUTHOR") "CERN DEM JLC"))
      (libsource (lib "ICs And Semiconductors") (part "IRF9910"))
    )
    (comp (ref "T9")
      (value "IRF9910Pbf")
      (footprint "SOIC127P600X175-8N")
      (description "Dual SO-8 MOSFET For POL Cconverter")
      (fields (field (name "MANUFACTURER") "INTERNATIONAL RECTIFIER") (field (name "AUTHOR") "CERN DEM JLC"))
      (libsource (lib "ICs And Semiconductors") (part "IRF9910"))
    )
    (comp (ref "T10")
      (value "BSH103")
      (footprint "SOT95P230X110-3N")
      (description "N-CHANNEL MOSFET WITH DIODE")
      (fields (field (name "MANUFACTURER") "NXP SEMICONDUCTORS") (field (name "AUTHOR") "CERN DEM JLC"))
      (libsource (lib "ICs And Semiconductors") (part "N-MOSFET-D 1G 2S 3D"))
    )
    (comp (ref "T11")
      (value "IRF9910Pbf")
      (footprint "SOIC127P600X175-8N")
      (description "Dual SO-8 MOSFET For POL Cconverter")
      (fields (field (name "MANUFACTURER") "INTERNATIONAL RECTIFIER") (field (name "AUTHOR") "CERN DEM JLC"))
      (libsource (lib "ICs And Semiconductors") (part "IRF9910"))
    )
  )
  (nets
    (net (code "1") (name "/EN_DC_DC") (class "Default")
      (node (ref "IC2") (pin "24") (pinfunction "EN1_24") (pintype "input"))
      (node (ref "IC2") (pin "7") (pinfunction "EN2_7") (pintype "input"))
      (node (ref "IC9") (pin "24") (pinfunction "EN1_24") (pintype "input"))
      (node (ref "IC9") (pin "7") (pinfunction "EN2_7") (pintype "input"))
      (node (ref "R60") (pin "1") (pinfunction "1_1") (pintype "passive"))
    )
    (net (code "2") (name "/EN_FMC1") (class "Default")
      (node (ref "IC11") (pin "24") (pinfunction "EN1_24") (pintype "input"))
      (node (ref "IC24") (pin "24") (pinfunction "EN1_24") (pintype "input"))
      (node (ref "R244") (pin "2") (pinfunction "2_2") (pintype "passive"))
    )
    (net (code "3") (name "/EN_FMC2") (class "Default")
      (node (ref "IC11") (pin "7") (pinfunction "EN2_7") (pintype "input"))
      (node (ref "IC24") (pin "7") (pinfunction "EN2_7") (pintype "input"))
      (node (ref "R195") (pin "2") (pinfunction "2_2") (pintype "passive"))
    )
    (net (code "4") (name "/RSTn") (class "Default")
      (node (ref "IC23") (pin "2") (pinfunction "~{RST}_2") (pintype "output"))
    )
    (net (code "5") (name "GND") (class "Default")
      (node (ref "B10") (pin "1") (pinfunction "1_1") (pintype "bidirectional"))
      (node (ref "C1") (pin "2") (pinfunction "2_2") (pintype "passive"))
      (node (ref "C119") (pin "1") (pinfunction "1_1") (pintype "passive"))
      (node (ref "C128") (pin "1") (pinfunction "1_1") (pintype "passive"))
      (node (ref "C135") (pin "1") (pinfunction "1_1") (pintype "passive"))
      (node (ref "C136") (pin "1") (pinfunction "1_1") (pintype "passive"))
      (node (ref "C137") (pin "1") (pinfunction "1_1") (pintype "passive"))
      (node (ref "C138") (pin "1") (pinfunction "1_1") (pintype "passive"))
      (node (ref "C139") (pin "1") (pinfunction "1_1") (pintype "passive"))
      (node (ref "C148") (pin "1") (pinfunction "1_1") (pintype "passive"))
      (node (ref "C163") (pin "1") (pinfunction "1_1") (pintype "passive"))
      (node (ref "C169") (pin "1") (pinfunction "1_1") (pintype "passive"))
      (node (ref "C173") (pin "1") (pinfunction "1_1") (pintype "passive"))
      (node (ref "C175") (pin "2") (pinfunction "2_2") (pintype "passive"))
      (node (ref "C176") (pin "1") (pinfunction "1_1") (pintype "passive"))
      (node (ref "C179") (pin "1") (pinfunction "1_1") (pintype "passive"))
      (node (ref "C180") (pin "1") (pinfunction "1_1") (pintype "passive"))
      (node (ref "C181") (pin "1") (pinfunction "1_1") (pintype "passive"))
      (node (ref "C182") (pin "1") (pinfunction "1_1") (pintype "passive"))
      (node (ref "C183") (pin "1") (pinfunction "1_1") (pintype "passive"))
      (node (ref "C207") (pin "1") (pinfunction "1_1") (pintype "passive"))
      (node (ref "C208") (pin "1") (pinfunction "1_1") (pintype "passive"))
      (node (ref "C209") (pin "1") (pinfunction "1_1") (pintype "passive"))
      (node (ref "C210") (pin "1") (pinfunction "1_1") (pintype "passive"))
      (node (ref "C211") (pin "2") (pinfunction "2_2") (pintype "passive"))
      (node (ref "C212") (pin "1") (pinfunction "1_1") (pintype "passive"))
      (node (ref "C218") (pin "1") (pinfunction "1_1") (pintype "passive"))
      (node (ref "C224") (pin "2") (pinfunction "2_2") (pintype "passive"))
      (node (ref "C225") (pin "2") (pinfunction "2_2") (pintype "passive"))
      (node (ref "C24") (pin "2") (pinfunction "2_2") (pintype "passive"))
      (node (ref "C241") (pin "2") (pinfunction "2_2") (pintype "passive"))
      (node (ref "C25") (pin "1") (pinfunction "1_1") (pintype "passive"))
      (node (ref "C28") (pin "1") (pinfunction "1_1") (pintype "passive"))
      (node (ref "C30") (pin "2") (pinfunction "2_2") (pintype "passive"))
      (node (ref "C31") (pin "1") (pinfunction "1_1") (pintype "passive"))
      (node (ref "C32") (pin "1") (pinfunction "1_1") (pintype "passive"))
      (node (ref "C33") (pin "1") (pinfunction "1_1") (pintype "passive"))
      (node (ref "C35") (pin "1") (pinfunction "1_1") (pintype "passive"))
      (node (ref "C37") (pin "2") (pinfunction "2_2") (pintype "passive"))
      (node (ref "C386") (pin "1") (pinfunction "1_1") (pintype "passive"))
      (node (ref "C41") (pin "2") (pinfunction "2_2") (pintype "passive"))
      (node (ref "C412") (pin "2") (pinfunction "2_2") (pintype "passive"))
      (node (ref "C413") (pin "2") (pinfunction "2_2") (pintype "passive"))
      (node (ref "C427") (pin "2") (pinfunction "2_2") (pintype "passive"))
      (node (ref "C428") (pin "2") (pinfunction "2_2") (pintype "passive"))
      (node (ref "C429") (pin "2") (pinfunction "2_2") (pintype "passive"))
      (node (ref "C43") (pin "1") (pinfunction "1_1") (pintype "passive"))
      (node (ref "C430") (pin "2") (pinfunction "2_2") (pintype "passive"))
      (node (ref "C431") (pin "2") (pinfunction "2_2") (pintype "passive"))
      (node (ref "C432") (pin "2") (pinfunction "2_2") (pintype "passive"))
      (node (ref "C433") (pin "2") (pinfunction "2_2") (pintype "passive"))
      (node (ref "C434") (pin "2") (pinfunction "2_2") (pintype "passive"))
      (node (ref "C435") (pin "2") (pinfunction "2_2") (pintype "passive"))
      (node (ref "C438") (pin "2") (pinfunction "2_2") (pintype "passive"))
      (node (ref "C439") (pin "2") (pinfunction "2_2") (pintype "passive"))
      (node (ref "C44") (pin "2") (pinfunction "2_2") (pintype "passive"))
      (node (ref "C440") (pin "2") (pinfunction "2_2") (pintype "passive"))
      (node (ref "C45") (pin "1") (pinfunction "1_1") (pintype "passive"))
      (node (ref "C46") (pin "1") (pinfunction "1_1") (pintype "passive"))
      (node (ref "C47") (pin "1") (pinfunction "1_1") (pintype "passive"))
      (node (ref "C48") (pin "1") (pinfunction "1_1") (pintype "passive"))
      (node (ref "C49") (pin "1") (pinfunction "1_1") (pintype "passive"))
      (node (ref "C5") (pin "1") (pinfunction "1_1") (pintype "passive"))
      (node (ref "C50") (pin "1") (pinfunction "1_1") (pintype "passive"))
      (node (ref "C51") (pin "1") (pinfunction "1_1") (pintype "passive"))
      (node (ref "C52") (pin "1") (pinfunction "1_1") (pintype "passive"))
      (node (ref "C55") (pin "1") (pinfunction "1_1") (pintype "passive"))
      (node (ref "C56") (pin "1") (pinfunction "1_1") (pintype "passive"))
      (node (ref "C60") (pin "2") (pinfunction "2_2") (pintype "passive"))
      (node (ref "C61") (pin "1") (pinfunction "1_1") (pintype "passive"))
      (node (ref "C62") (pin "1") (pinfunction "1_1") (pintype "passive"))
      (node (ref "C63") (pin "1") (pinfunction "1_1") (pintype "passive"))
      (node (ref "C65") (pin "1") (pinfunction "1_1") (pintype "passive"))
      (node (ref "C66") (pin "1") (pinfunction "1_1") (pintype "passive"))
      (node (ref "C67") (pin "2") (pinfunction "2_2") (pintype "passive"))
      (node (ref "C68") (pin "1") (pinfunction "1_1") (pintype "passive"))
      (node (ref "C70") (pin "2") (pinfunction "2_2") (pintype "passive"))
      (node (ref "C71") (pin "2") (pinfunction "2_2") (pintype "passive"))
      (node (ref "C72") (pin "1") (pinfunction "1_1") (pintype "passive"))
      (node (ref "C73") (pin "1") (pinfunction "1_1") (pintype "passive"))
      (node (ref "C75") (pin "1") (pinfunction "1_1") (pintype "passive"))
      (node (ref "C77") (pin "1") (pinfunction "1_1") (pintype "passive"))
      (node (ref "C78") (pin "1") (pinfunction "1_1") (pintype "passive"))
      (node (ref "C79") (pin "2") (pinfunction "2_2") (pintype "passive"))
      (node (ref "C80") (pin "2") (pinfunction "2_2") (pintype "passive"))
      (node (ref "C81") (pin "1") (pinfunction "1_1") (pintype "passive"))
      (node (ref "C82") (pin "2") (pinfunction "2_2") (pintype "passive"))
      (node (ref "C83") (pin "1") (pinfunction "1_1") (pintype "passive"))
      (node (ref "C85") (pin "1") (pinfunction "1_1") (pintype "passive"))
      (node (ref "C86") (pin "1") (pinfunction "1_1") (pintype "passive"))
      (node (ref "C87") (pin "2") (pinfunction "2_2") (pintype "passive"))
      (node (ref "C88") (pin "2") (pinfunction "2_2") (pintype "passive"))
      (node (ref "C90") (pin "1") (pinfunction "1_1") (pintype "passive"))
      (node (ref "C91") (pin "2") (pinfunction "2_2") (pintype "passive"))
      (node (ref "C93") (pin "1") (pinfunction "1_1") (pintype "passive"))
      (node (ref "D1") (pin "2") (pinfunction "A_2") (pintype "passive"))
      (node (ref "IC11") (pin "12") (pinfunction "PGND2_12") (pintype "power_in"))
      (node (ref "IC11") (pin "14") (pinfunction "TEST2_14") (pintype "input"))
      (node (ref "IC11") (pin "19") (pinfunction "PGND1_19") (pintype "power_in"))
      (node (ref "IC11") (pin "25") (pinfunction "EP_25") (pintype "power_in"))
      (node (ref "IC11") (pin "3") (pinfunction "GND_3") (pintype "power_in"))
      (node (ref "IC11") (pin "4") (pinfunction "TEST1_4") (pintype "output"))
      (node (ref "IC2") (pin "12") (pinfunction "PGND2_12") (pintype "power_in"))
      (node (ref "IC2") (pin "14") (pinfunction "TEST2_14") (pintype "input"))
      (node (ref "IC2") (pin "19") (pinfunction "PGND1_19") (pintype "power_in"))
      (node (ref "IC2") (pin "25") (pinfunction "EP_25") (pintype "power_in"))
      (node (ref "IC2") (pin "3") (pinfunction "GND_3") (pintype "power_in"))
      (node (ref "IC2") (pin "4") (pinfunction "TEST1_4") (pintype "output"))
      (node (ref "IC23") (pin "1") (pinfunction "VSS_1") (pintype "power_in"))
      (node (ref "IC24") (pin "12") (pinfunction "PGND2_12") (pintype "power_in"))
      (node (ref "IC24") (pin "14") (pinfunction "TEST2_14") (pintype "input"))
      (node (ref "IC24") (pin "19") (pinfunction "PGND1_19") (pintype "power_in"))
      (node (ref "IC24") (pin "25") (pinfunction "EP_25") (pintype "power_in"))
      (node (ref "IC24") (pin "3") (pinfunction "GND_3") (pintype "power_in"))
      (node (ref "IC24") (pin "4") (pinfunction "TEST1_4") (pintype "output"))
      (node (ref "IC8") (pin "11") (pinfunction "EP_11") (pintype "power_in"))
      (node (ref "IC8") (pin "4") (pinfunction "PGND_4") (pintype "power_in"))
      (node (ref "IC8") (pin "8") (pinfunction "GND_8") (pintype "power_in"))
      (node (ref "IC9") (pin "12") (pinfunction "PGND2_12") (pintype "power_in"))
      (node (ref "IC9") (pin "14") (pinfunction "TEST2_14") (pintype "input"))
      (node (ref "IC9") (pin "19") (pinfunction "PGND1_19") (pintype "power_in"))
      (node (ref "IC9") (pin "25") (pinfunction "EP_25") (pintype "power_in"))
      (node (ref "IC9") (pin "3") (pinfunction "GND_3") (pintype "power_in"))
      (node (ref "IC9") (pin "4") (pinfunction "TEST1_4") (pintype "output"))
      (node (ref "J1") (pin "2") (pinfunction "2_2") (pintype "bidirectional"))
      (node (ref "J1") (pin "3") (pinfunction "3_3") (pintype "bidirectional"))
      (node (ref "LD1") (pin "1") (pinfunction "C_1") (pintype "passive"))
      (node (ref "LD11") (pin "1") (pinfunction "C_1") (pintype "passive"))
      (node (ref "LD13") (pin "1") (pinfunction "C_1") (pintype "passive"))
      (node (ref "LD14") (pin "1") (pinfunction "C_1") (pintype "passive"))
      (node (ref "LD15") (pin "1") (pinfunction "C_1") (pintype "passive"))
      (node (ref "LD16") (pin "1") (pinfunction "C_1") (pintype "passive"))
      (node (ref "LD4") (pin "1") (pinfunction "C_1") (pintype "passive"))
      (node (ref "R11") (pin "1") (pinfunction "1_1") (pintype "passive"))
      (node (ref "R114") (pin "1") (pinfunction "1_1") (pintype "passive"))
      (node (ref "R119") (pin "1") (pinfunction "1_1") (pintype "passive"))
      (node (ref "R12") (pin "1") (pinfunction "1_1") (pintype "passive"))
      (node (ref "R120") (pin "1") (pinfunction "1_1") (pintype "passive"))
      (node (ref "R121") (pin "1") (pinfunction "1_1") (pintype "passive"))
      (node (ref "R123") (pin "2") (pinfunction "2_2") (pintype "passive"))
      (node (ref "R128") (pin "1") (pinfunction "1_1") (pintype "passive"))
      (node (ref "R146") (pin "2") (pinfunction "2_2") (pintype "passive"))
      (node (ref "R194") (pin "1") (pinfunction "1_1") (pintype "passive"))
      (node (ref "R195") (pin "1") (pinfunction "1_1") (pintype "passive"))
      (node (ref "R208") (pin "1") (pinfunction "1_1") (pintype "passive"))
      (node (ref "R22") (pin "2") (pinfunction "2_2") (pintype "passive"))
      (node (ref "R24") (pin "2") (pinfunction "2_2") (pintype "passive"))
      (node (ref "R244") (pin "1") (pinfunction "1_1") (pintype "passive"))
      (node (ref "R26") (pin "2") (pinfunction "2_2") (pintype "passive"))
      (node (ref "R27") (pin "1") (pinfunction "1_1") (pintype "passive"))
      (node (ref "R31") (pin "1") (pinfunction "1_1") (pintype "passive"))
      (node (ref "R4") (pin "1") (pinfunction "1_1") (pintype "passive"))
      (node (ref "R6") (pin "1") (pinfunction "1_1") (pintype "passive"))
      (node (ref "R8") (pin "1") (pinfunction "1_1") (pintype "passive"))
      (node (ref "T1") (pin "1") (pinfunction "S_1") (pintype "passive"))
      (node (ref "T10") (pin "2") (pinfunction "S_2") (pintype "passive"))
      (node (ref "T11") (pin "1") (pinfunction "S_1") (pintype "passive"))
      (node (ref "T2") (pin "1") (pinfunction "S_1") (pintype "passive"))
      (node (ref "T3") (pin "1") (pinfunction "S_1") (pintype "passive"))
      (node (ref "T4") (pin "1") (pinfunction "S_1") (pintype "passive"))
      (node (ref "T5") (pin "2") (pinfunction "S_2") (pintype "passive"))
      (node (ref "T6") (pin "2") (pinfunction "S_2") (pintype "passive"))
      (node (ref "T7") (pin "1") (pinfunction "S_1") (pintype "passive"))
      (node (ref "T8") (pin "1") (pinfunction "S_1") (pintype "passive"))
      (node (ref "T9") (pin "1") (pinfunction "S_1") (pintype "passive"))
    )
    (net (code "6") (name "Net-(IC2-DRVH1)") (class "Default")
      (node (ref "IC2") (pin "22") (pinfunction "DRVH1_22") (pintype "output"))
      (node (ref "T7") (pin "4") (pinfunction "G_4") (pintype "passive"))
    )
    (net (code "7") (name "Net-(IC2-DRVH2)") (class "Default")
      (node (ref "IC2") (pin "9") (pinfunction "DRVH2_9") (pintype "output"))
      (node (ref "T9") (pin "4") (pinfunction "G_4") (pintype "passive"))
    )
    (net (code "8") (name "Net-(IC2-DRVL1)") (class "Default")
      (node (ref "IC2") (pin "20") (pinfunction "DRVL1_20") (pintype "output"))
      (node (ref "T7") (pin "2") (pinfunction "G_2") (pintype "passive"))
    )
    (net (code "9") (name "Net-(IC2-DRVL2)") (class "Default")
      (node (ref "IC2") (pin "11") (pinfunction "DRVL2_11") (pintype "output"))
      (node (ref "T8") (pin "2") (pinfunction "G_2") (pintype "passive"))
    )
    (net (code "10") (name "Net-(IC2-SW1)") (class "Default")
      (node (ref "C167") (pin "2") (pinfunction "2_2") (pintype "passive"))
      (node (ref "IC2") (pin "21") (pinfunction "SW1_21") (pintype "bidirectional"))
      (node (ref "L13") (pin "1") (pinfunction "1_1") (pintype "passive"))
      (node (ref "T7") (pin "3") (pinfunction "S_3") (pintype "passive"))
      (node (ref "T7") (pin "7") (pinfunction "D_7") (pintype "passive"))
      (node (ref "T7") (pin "8") (pinfunction "D_8") (pintype "passive"))
    )
    (net (code "11") (name "Net-(IC2-SW2)") (class "Default")
      (node (ref "C195") (pin "2") (pinfunction "2_2") (pintype "passive"))
      (node (ref "IC2") (pin "10") (pinfunction "SW2_10") (pintype "bidirectional"))
      (node (ref "L14") (pin "1") (pinfunction "1_1") (pintype "passive"))
      (node (ref "T8") (pin "7") (pinfunction "D_7") (pintype "passive"))
      (node (ref "T8") (pin "8") (pinfunction "D_8") (pintype "passive"))
      (node (ref "T9") (pin "3") (pinfunction "S_3") (pintype "passive"))
    )
    (net (code "12") (name "Net-(IC2-TRIP1)") (class "Default")
      (node (ref "IC2") (pin "18") (pinfunction "TRIP1_18") (pintype "input"))
      (node (ref "R189") (pin "2") (pinfunction "2_2") (pintype "passive"))
    )
    (net (code "13") (name "Net-(IC2-TRIP2)") (class "Default")
      (node (ref "IC2") (pin "13") (pinfunction "TRIP2_13") (pintype "input"))
      (node (ref "R194") (pin "2") (pinfunction "2_2") (pintype "passive"))
    )
    (net (code "14") (name "Net-(IC2-V5FILT)") (class "Default")
      (node (ref "C33") (pin "2") (pinfunction "2_2") (pintype "passive"))
      (node (ref "IC2") (pin "15") (pinfunction "V5FILT_15") (pintype "input"))
    )
    (net (code "15") (name "Net-(IC2-VBST1)") (class "Default")
      (node (ref "C167") (pin "1") (pinfunction "1_1") (pintype "passive"))
      (node (ref "IC2") (pin "23") (pinfunction "VBST1_23") (pintype "input"))
    )
    (net (code "16") (name "Net-(IC2-VBST2)") (class "Default")
      (node (ref "C195") (pin "1") (pinfunction "1_1") (pintype "passive"))
      (node (ref "IC2") (pin "8") (pinfunction "VBST2_8") (pintype "input"))
    )
    (net (code "17") (name "Net-(IC2-VFB1)") (class "Default")
      (node (ref "IC2") (pin "2") (pinfunction "VFB1_2") (pintype "input"))
      (node (ref "R128") (pin "2") (pinfunction "2_2") (pintype "passive"))
      (node (ref "R168") (pin "1") (pinfunction "1_1") (pintype "passive"))
    )
    (net (code "18") (name "Net-(IC2-VFB2)") (class "Default")
      (node (ref "IC2") (pin "5") (pinfunction "VFB2_5") (pintype "input"))
      (node (ref "R129") (pin "2") (pinfunction "2_2") (pintype "passive"))
      (node (ref "R26") (pin "1") (pinfunction "1_1") (pintype "passive"))
    )
    (net (code "19") (name "Net-(IC2-VREG5)") (class "Default")
      (node (ref "C35") (pin "2") (pinfunction "2_2") (pintype "passive"))
      (node (ref "IC2") (pin "16") (pinfunction "VREG5_16") (pintype "output"))
    )
    (net (code "20") (name "Net-(IC8-PGOOD)") (class "Default")
      (node (ref "IC8") (pin "9") (pinfunction "PGOOD_9") (pintype "output"))
      (node (ref "R150") (pin "1") (pinfunction "1_1") (pintype "passive"))
      (node (ref "T6") (pin "1") (pinfunction "G_1") (pintype "passive"))
    )
    (net (code "21") (name "Net-(IC8-REFIN)") (class "Default")
      (node (ref "C43") (pin "2") (pinfunction "2_2") (pintype "passive"))
      (node (ref "IC8") (pin "1") (pinfunction "REFIN_1") (pintype "input"))
      (node (ref "R130") (pin "1") (pinfunction "1_1") (pintype "passive"))
      (node (ref "R146") (pin "1") (pinfunction "1_1") (pintype "passive"))
    )
    (net (code "22") (name "Net-(IC9-DRVH1)") (class "Default")
      (node (ref "IC9") (pin "22") (pinfunction "DRVH1_22") (pintype "output"))
      (node (ref "T3") (pin "4") (pinfunction "G_4") (pintype "passive"))
    )
    (net (code "23") (name "Net-(IC9-DRVH2)") (class "Default")
      (node (ref "IC9") (pin "9") (pinfunction "DRVH2_9") (pintype "output"))
      (node (ref "T4") (pin "4") (pinfunction "G_4") (pintype "passive"))
    )
    (net (code "24") (name "Net-(IC9-DRVL1)") (class "Default")
      (node (ref "IC9") (pin "20") (pinfunction "DRVL1_20") (pintype "output"))
      (node (ref "T3") (pin "2") (pinfunction "G_2") (pintype "passive"))
    )
    (net (code "25") (name "Net-(IC9-DRVL2)") (class "Default")
      (node (ref "IC9") (pin "11") (pinfunction "DRVL2_11") (pintype "output"))
      (node (ref "T4") (pin "2") (pinfunction "G_2") (pintype "passive"))
    )
    (net (code "26") (name "Net-(IC9-SW1)") (class "Default")
      (node (ref "C38") (pin "2") (pinfunction "2_2") (pintype "passive"))
      (node (ref "IC9") (pin "21") (pinfunction "SW1_21") (pintype "bidirectional"))
      (node (ref "L16") (pin "1") (pinfunction "1_1") (pintype "passive"))
      (node (ref "T3") (pin "3") (pinfunction "S_3") (pintype "passive"))
      (node (ref "T3") (pin "7") (pinfunction "D_7") (pintype "passive"))
      (node (ref "T3") (pin "8") (pinfunction "D_8") (pintype "passive"))
    )
    (net (code "27") (name "Net-(IC9-SW2)") (class "Default")
      (node (ref "C39") (pin "2") (pinfunction "2_2") (pintype "passive"))
      (node (ref "IC9") (pin "10") (pinfunction "SW2_10") (pintype "bidirectional"))
      (node (ref "L1") (pin "1") (pinfunction "1_1") (pintype "passive"))
      (node (ref "T4") (pin "3") (pinfunction "S_3") (pintype "passive"))
      (node (ref "T4") (pin "7") (pinfunction "D_7") (pintype "passive"))
      (node (ref "T4") (pin "8") (pinfunction "D_8") (pintype "passive"))
    )
    (net (code "28") (name "Net-(IC9-TRIP1)") (class "Default")
      (node (ref "IC9") (pin "18") (pinfunction "TRIP1_18") (pintype "input"))
      (node (ref "R11") (pin "2") (pinfunction "2_2") (pintype "passive"))
    )
    (net (code "29") (name "Net-(IC9-TRIP2)") (class "Default")
      (node (ref "IC9") (pin "13") (pinfunction "TRIP2_13") (pintype "input"))
      (node (ref "R12") (pin "2") (pinfunction "2_2") (pintype "passive"))
      (node (ref "R120") (pin "2") (pinfunction "2_2") (pintype "passive"))
    )
    (net (code "30") (name "Net-(IC9-V5FILT)") (class "Default")
      (node (ref "C5") (pin "2") (pinfunction "2_2") (pintype "passive"))
      (node (ref "IC9") (pin "15") (pinfunction "V5FILT_15") (pintype "input"))
    )
    (net (code "31") (name "Net-(IC9-VBST1)") (class "Default")
      (node (ref "C38") (pin "1") (pinfunction "1_1") (pintype "passive"))
      (node (ref "IC9") (pin "23") (pinfunction "VBST1_23") (pintype "input"))
    )
    (net (code "32") (name "Net-(IC9-VBST2)") (class "Default")
      (node (ref "C39") (pin "1") (pinfunction "1_1") (pintype "passive"))
      (node (ref "IC9") (pin "8") (pinfunction "VBST2_8") (pintype "input"))
    )
    (net (code "33") (name "Net-(IC9-VFB1)") (class "Default")
      (node (ref "IC9") (pin "2") (pinfunction "VFB1_2") (pintype "input"))
      (node (ref "R118") (pin "1") (pinfunction "1_1") (pintype "passive"))
      (node (ref "R8") (pin "2") (pinfunction "2_2") (pintype "passive"))
    )
    (net (code "34") (name "Net-(IC9-VFB2)") (class "Default")
      (node (ref "IC9") (pin "5") (pinfunction "VFB2_5") (pintype "input"))
      (node (ref "R117") (pin "2") (pinfunction "2_2") (pintype "passive"))
      (node (ref "R22") (pin "1") (pinfunction "1_1") (pintype "passive"))
    )
    (net (code "35") (name "Net-(IC9-VREG5)") (class "Default")
      (node (ref "C173") (pin "2") (pinfunction "2_2") (pintype "passive"))
      (node (ref "IC9") (pin "16") (pinfunction "VREG5_16") (pintype "output"))
    )
    (net (code "36") (name "Net-(IC11-DRVH1)") (class "Default")
      (node (ref "IC11") (pin "22") (pinfunction "DRVH1_22") (pintype "output"))
      (node (ref "T11") (pin "4") (pinfunction "G_4") (pintype "passive"))
    )
    (net (code "37") (name "Net-(IC11-DRVH2)") (class "Default")
      (node (ref "IC11") (pin "9") (pinfunction "DRVH2_9") (pintype "output"))
      (node (ref "T1") (pin "4") (pinfunction "G_4") (pintype "passive"))
    )
    (net (code "38") (name "Net-(IC11-DRVL1)") (class "Default")
      (node (ref "IC11") (pin "20") (pinfunction "DRVL1_20") (pintype "output"))
      (node (ref "T11") (pin "2") (pinfunction "G_2") (pintype "passive"))
    )
    (net (code "39") (name "Net-(IC11-DRVL2)") (class "Default")
      (node (ref "IC11") (pin "11") (pinfunction "DRVL2_11") (pintype "output"))
      (node (ref "T1") (pin "2") (pinfunction "G_2") (pintype "passive"))
    )
    (net (code "40") (name "Net-(IC11-SW1)") (class "Default")
      (node (ref "C89") (pin "2") (pinfunction "2_2") (pintype "passive"))
      (node (ref "IC11") (pin "21") (pinfunction "SW1_21") (pintype "bidirectional"))
      (node (ref "L4") (pin "1") (pinfunction "1_1") (pintype "passive"))
      (node (ref "T11") (pin "3") (pinfunction "S_3") (pintype "passive"))
      (node (ref "T11") (pin "7") (pinfunction "D_7") (pintype "passive"))
      (node (ref "T11") (pin "8") (pinfunction "D_8") (pintype "passive"))
    )
    (net (code "41") (name "Net-(IC11-SW2)") (class "Default")
      (node (ref "C166") (pin "2") (pinfunction "2_2") (pintype "passive"))
      (node (ref "IC11") (pin "10") (pinfunction "SW2_10") (pintype "bidirectional"))
      (node (ref "L12") (pin "1") (pinfunction "1_1") (pintype "passive"))
      (node (ref "T1") (pin "3") (pinfunction "S_3") (pintype "passive"))
      (node (ref "T1") (pin "7") (pinfunction "D_7") (pintype "passive"))
      (node (ref "T1") (pin "8") (pinfunction "D_8") (pintype "passive"))
    )
    (net (code "42") (name "Net-(IC11-TRIP1)") (class "Default")
      (node (ref "IC11") (pin "18") (pinfunction "TRIP1_18") (pintype "input"))
      (node (ref "R114") (pin "2") (pinfunction "2_2") (pintype "passive"))
    )
    (net (code "43") (name "Net-(IC11-TRIP2)") (class "Default")
      (node (ref "IC11") (pin "13") (pinfunction "TRIP2_13") (pintype "input"))
      (node (ref "R121") (pin "2") (pinfunction "2_2") (pintype "passive"))
    )
    (net (code "44") (name "Net-(IC11-V5FILT)") (class "Default")
      (node (ref "C386") (pin "2") (pinfunction "2_2") (pintype "passive"))
      (node (ref "IC11") (pin "15") (pinfunction "V5FILT_15") (pintype "input"))
    )
    (net (code "45") (name "Net-(IC11-VBST1)") (class "Default")
      (node (ref "C89") (pin "1") (pinfunction "1_1") (pintype "passive"))
      (node (ref "IC11") (pin "23") (pinfunction "VBST1_23") (pintype "input"))
    )
    (net (code "46") (name "Net-(IC11-VBST2)") (class "Default")
      (node (ref "C166") (pin "1") (pinfunction "1_1") (pintype "passive"))
      (node (ref "IC11") (pin "8") (pinfunction "VBST2_8") (pintype "input"))
    )
    (net (code "47") (name "Net-(IC11-VFB1)") (class "Default")
      (node (ref "IC11") (pin "2") (pinfunction "VFB1_2") (pintype "input"))
      (node (ref "R1") (pin "1") (pinfunction "1_1") (pintype "passive"))
      (node (ref "R4") (pin "2") (pinfunction "2_2") (pintype "passive"))
    )
    (net (code "48") (name "Net-(IC11-VFB2)") (class "Default")
      (node (ref "IC11") (pin "5") (pinfunction "VFB2_5") (pintype "input"))
      (node (ref "R5") (pin "1") (pinfunction "1_1") (pintype "passive"))
      (node (ref "R6") (pin "2") (pinfunction "2_2") (pintype "passive"))
    )
    (net (code "49") (name "Net-(IC11-VREG5)") (class "Default")
      (node (ref "C207") (pin "2") (pinfunction "2_2") (pintype "passive"))
      (node (ref "IC11") (pin "16") (pinfunction "VREG5_16") (pintype "output"))
    )
    (net (code "50") (name "Net-(IC24-DRVH1)") (class "Default")
      (node (ref "IC24") (pin "22") (pinfunction "DRVH1_22") (pintype "output"))
      (node (ref "T2") (pin "4") (pinfunction "G_4") (pintype "passive"))
    )
    (net (code "51") (name "Net-(IC24-DRVH2)") (class "Default")
      (node (ref "IC24") (pin "9") (pinfunction "DRVH2_9") (pintype "output"))
      (node (ref "T8") (pin "4") (pinfunction "G_4") (pintype "passive"))
    )
    (net (code "52") (name "Net-(IC24-DRVL1)") (class "Default")
      (node (ref "IC24") (pin "20") (pinfunction "DRVL1_20") (pintype "output"))
      (node (ref "T2") (pin "2") (pinfunction "G_2") (pintype "passive"))
    )
    (net (code "53") (name "Net-(IC24-DRVL2)") (class "Default")
      (node (ref "IC24") (pin "11") (pinfunction "DRVL2_11") (pintype "output"))
      (node (ref "T9") (pin "2") (pinfunction "G_2") (pintype "passive"))
    )
    (net (code "54") (name "Net-(IC24-SW1)") (class "Default")
      (node (ref "C40") (pin "2") (pinfunction "2_2") (pintype "passive"))
      (node (ref "IC24") (pin "21") (pinfunction "SW1_21") (pintype "bidirectional"))
      (node (ref "L2") (pin "1") (pinfunction "1_1") (pintype "passive"))
      (node (ref "T2") (pin "3") (pinfunction "S_3") (pintype "passive"))
      (node (ref "T2") (pin "7") (pinfunction "D_7") (pintype "passive"))
      (node (ref "T2") (pin "8") (pinfunction "D_8") (pintype "passive"))
    )
    (net (code "55") (name "Net-(IC24-SW2)") (class "Default")
      (node (ref "C69") (pin "2") (pinfunction "2_2") (pintype "passive"))
      (node (ref "IC24") (pin "10") (pinfunction "SW2_10") (pintype "bidirectional"))
      (node (ref "L3") (pin "1") (pinfunction "1_1") (pintype "passive"))
      (node (ref "T8") (pin "3") (pinfunction "S_3") (pintype "passive"))
      (node (ref "T9") (pin "7") (pinfunction "D_7") (pintype "passive"))
      (node (ref "T9") (pin "8") (pinfunction "D_8") (pintype "passive"))
    )
    (net (code "56") (name "Net-(IC24-TRIP1)") (class "Default")
      (node (ref "IC24") (pin "18") (pinfunction "TRIP1_18") (pintype "input"))
      (node (ref "R27") (pin "2") (pinfunction "2_2") (pintype "passive"))
    )
    (net (code "57") (name "Net-(IC24-TRIP2)") (class "Default")
      (node (ref "IC24") (pin "13") (pinfunction "TRIP2_13") (pintype "input"))
      (node (ref "R31") (pin "2") (pinfunction "2_2") (pintype "passive"))
    )
    (net (code "58") (name "Net-(IC24-V5FILT)") (class "Default")
      (node (ref "C32") (pin "2") (pinfunction "2_2") (pintype "passive"))
      (node (ref "IC24") (pin "15") (pinfunction "V5FILT_15") (pintype "input"))
    )
    (net (code "59") (name "Net-(IC24-VBST1)") (class "Default")
      (node (ref "C40") (pin "1") (pinfunction "1_1") (pintype "passive"))
      (node (ref "IC24") (pin "23") (pinfunction "VBST1_23") (pintype "input"))
    )
    (net (code "60") (name "Net-(IC24-VBST2)") (class "Default")
      (node (ref "C69") (pin "1") (pinfunction "1_1") (pintype "passive"))
      (node (ref "IC24") (pin "8") (pinfunction "VBST2_8") (pintype "input"))
    )
    (net (code "61") (name "Net-(IC24-VFB1)") (class "Default")
      (node (ref "IC24") (pin "2") (pinfunction "VFB1_2") (pintype "input"))
      (node (ref "R10") (pin "2") (pinfunction "2_2") (pintype "passive"))
      (node (ref "R123") (pin "1") (pinfunction "1_1") (pintype "passive"))
    )
    (net (code "62") (name "Net-(IC24-VFB2)") (class "Default")
      (node (ref "IC24") (pin "5") (pinfunction "VFB2_5") (pintype "input"))
      (node (ref "R23") (pin "2") (pinfunction "2_2") (pintype "passive"))
      (node (ref "R24") (pin "1") (pinfunction "1_1") (pintype "passive"))
    )
    (net (code "63") (name "Net-(IC24-VREG5)") (class "Default")
      (node (ref "C63") (pin "2") (pinfunction "2_2") (pintype "passive"))
      (node (ref "IC24") (pin "16") (pinfunction "VREG5_16") (pintype "output"))
    )
    (net (code "64") (name "Net-(LD1-A)") (class "Default")
      (node (ref "LD1") (pin "2") (pinfunction "A_2") (pintype "passive"))
      (node (ref "R115") (pin "1") (pinfunction "1_1") (pintype "passive"))
    )
    (net (code "65") (name "Net-(LD2-A)") (class "Default")
      (node (ref "LD2") (pin "2") (pinfunction "A_2") (pintype "passive"))
      (node (ref "R106") (pin "1") (pinfunction "1_1") (pintype "passive"))
    )
    (net (code "66") (name "Net-(LD2-C)") (class "Default")
      (node (ref "LD2") (pin "1") (pinfunction "C_1") (pintype "passive"))
      (node (ref "T5") (pin "3") (pinfunction "D_3") (pintype "passive"))
    )
    (net (code "67") (name "Net-(LD3-A)") (class "Default")
      (node (ref "LD3") (pin "2") (pinfunction "A_2") (pintype "passive"))
      (node (ref "R111") (pin "1") (pinfunction "1_1") (pintype "passive"))
    )
    (net (code "68") (name "Net-(LD3-C)") (class "Default")
      (node (ref "LD3") (pin "1") (pinfunction "C_1") (pintype "passive"))
      (node (ref "T10") (pin "3") (pinfunction "D_3") (pintype "passive"))
    )
    (net (code "69") (name "Net-(LD4-A)") (class "Default")
      (node (ref "LD4") (pin "2") (pinfunction "A_2") (pintype "passive"))
      (node (ref "R116") (pin "1") (pinfunction "1_1") (pintype "passive"))
    )
    (net (code "70") (name "Net-(LD6-C)") (class "Default")
      (node (ref "LD6") (pin "1") (pinfunction "C_1") (pintype "passive"))
      (node (ref "R119") (pin "2") (pinfunction "2_2") (pintype "passive"))
    )
    (net (code "71") (name "Net-(LD11-A)") (class "Default")
      (node (ref "LD11") (pin "2") (pinfunction "A_2") (pintype "passive"))
      (node (ref "R125") (pin "1") (pinfunction "1_1") (pintype "passive"))
    )
    (net (code "72") (name "Net-(LD13-A)") (class "Default")
      (node (ref "LD13") (pin "2") (pinfunction "A_2") (pintype "passive"))
      (node (ref "R113") (pin "1") (pinfunction "1_1") (pintype "passive"))
    )
    (net (code "73") (name "Net-(LD14-A)") (class "Default")
      (node (ref "LD14") (pin "2") (pinfunction "A_2") (pintype "passive"))
      (node (ref "R124") (pin "1") (pinfunction "1_1") (pintype "passive"))
    )
    (net (code "74") (name "Net-(LD15-A)") (class "Default")
      (node (ref "LD15") (pin "2") (pinfunction "A_2") (pintype "passive"))
      (node (ref "R112") (pin "1") (pinfunction "1_1") (pintype "passive"))
    )
    (net (code "75") (name "Net-(LD16-A)") (class "Default")
      (node (ref "LD16") (pin "2") (pinfunction "A_2") (pintype "passive"))
      (node (ref "R108") (pin "1") (pinfunction "1_1") (pintype "passive"))
    )
    (net (code "76") (name "Net-(LD19-A)") (class "Default")
      (node (ref "LD19") (pin "2") (pinfunction "A_2") (pintype "passive"))
      (node (ref "R134") (pin "1") (pinfunction "1_1") (pintype "passive"))
    )
    (net (code "77") (name "Net-(LD19-C)") (class "Default")
      (node (ref "LD19") (pin "1") (pinfunction "C_1") (pintype "passive"))
      (node (ref "T6") (pin "3") (pinfunction "D_3") (pintype "passive"))
    )
    (net (code "78") (name "Net-(R189-Pad1)") (class "Default")
      (node (ref "R189") (pin "1") (pinfunction "1_1") (pintype "passive"))
      (node (ref "R208") (pin "2") (pinfunction "2_2") (pintype "passive"))
    )
    (net (code "79") (name "P1V2") (class "Default")
      (node (ref "B1") (pin "1") (pinfunction "1_1") (pintype "bidirectional"))
      (node (ref "C169") (pin "2") (pinfunction "2_2") (pintype "passive"))
      (node (ref "C183") (pin "2") (pinfunction "2_2") (pintype "passive"))
      (node (ref "C209") (pin "2") (pinfunction "2_2") (pintype "passive"))
      (node (ref "C210") (pin "2") (pinfunction "2_2") (pintype "passive"))
      (node (ref "C212") (pin "2") (pinfunction "2_2") (pintype "passive"))
      (node (ref "C224") (pin "1") (pinfunction "1_1") (pintype "passive"))
      (node (ref "C225") (pin "1") (pinfunction "1_1") (pintype "passive"))
      (node (ref "C45") (pin "2") (pinfunction "2_2") (pintype "passive"))
      (node (ref "C46") (pin "2") (pinfunction "2_2") (pintype "passive"))
      (node (ref "C47") (pin "2") (pinfunction "2_2") (pintype "passive"))
      (node (ref "C48") (pin "2") (pinfunction "2_2") (pintype "passive"))
      (node (ref "C49") (pin "2") (pinfunction "2_2") (pintype "passive"))
      (node (ref "IC2") (pin "6") (pinfunction "VO2_6") (pintype "input"))
      (node (ref "L14") (pin "2") (pinfunction "2_2") (pintype "passive"))
      (node (ref "R129") (pin "1") (pinfunction "1_1") (pintype "passive"))
      (node (ref "T10") (pin "1") (pinfunction "G_1") (pintype "passive"))
    )
    (net (code "80") (name "P1V5") (class "Default")
      (node (ref "C163") (pin "2") (pinfunction "2_2") (pintype "passive"))
      (node (ref "C211") (pin "1") (pinfunction "1_1") (pintype "passive"))
      (node (ref "C66") (pin "2") (pinfunction "2_2") (pintype "passive"))
      (node (ref "C90") (pin "2") (pinfunction "2_2") (pintype "passive"))
      (node (ref "C93") (pin "2") (pinfunction "2_2") (pintype "passive"))
      (node (ref "IC2") (pin "1") (pinfunction "VO1_1") (pintype "input"))
      (node (ref "IC8") (pin "2") (pinfunction "VLDOIN_2") (pintype "input"))
      (node (ref "L13") (pin "2") (pinfunction "2_2") (pintype "passive"))
      (node (ref "R130") (pin "2") (pinfunction "2_2") (pintype "passive"))
      (node (ref "R168") (pin "2") (pinfunction "2_2") (pintype "passive"))
      (node (ref "T5") (pin "1") (pinfunction "G_1") (pintype "passive"))
    )
    (net (code "81") (name "P1V8") (class "Default")
      (node (ref "B2") (pin "1") (pinfunction "1_1") (pintype "bidirectional"))
    )
    (net (code "82") (name "P2V5") (class "Default")
      (node (ref "B9") (pin "1") (pinfunction "1_1") (pintype "bidirectional"))
      (node (ref "C128") (pin "2") (pinfunction "2_2") (pintype "passive"))
      (node (ref "C139") (pin "2") (pinfunction "2_2") (pintype "passive"))
      (node (ref "C148") (pin "2") (pinfunction "2_2") (pintype "passive"))
      (node (ref "C60") (pin "1") (pinfunction "1_1") (pintype "passive"))
      (node (ref "C72") (pin "2") (pinfunction "2_2") (pintype "passive"))
      (node (ref "C77") (pin "2") (pinfunction "2_2") (pintype "passive"))
      (node (ref "IC9") (pin "6") (pinfunction "VO2_6") (pintype "input"))
      (node (ref "L1") (pin "2") (pinfunction "2_2") (pintype "passive"))
      (node (ref "R117") (pin "1") (pinfunction "1_1") (pintype "passive"))
    )
    (net (code "83") (name "P2V5_FMC1") (class "Default")
      (node (ref "C25") (pin "2") (pinfunction "2_2") (pintype "passive"))
      (node (ref "C28") (pin "2") (pinfunction "2_2") (pintype "passive"))
      (node (ref "C73") (pin "2") (pinfunction "2_2") (pintype "passive"))
      (node (ref "C75") (pin "2") (pinfunction "2_2") (pintype "passive"))
      (node (ref "C78") (pin "2") (pinfunction "2_2") (pintype "passive"))
      (node (ref "C79") (pin "1") (pinfunction "1_1") (pintype "passive"))
      (node (ref "IC24") (pin "1") (pinfunction "VO1_1") (pintype "input"))
      (node (ref "L2") (pin "2") (pinfunction "2_2") (pintype "passive"))
      (node (ref "R10") (pin "1") (pinfunction "1_1") (pintype "passive"))
      (node (ref "R115") (pin "2") (pinfunction "2_2") (pintype "passive"))
    )
    (net (code "84") (name "P2V5_FMC2") (class "Default")
      (node (ref "C50") (pin "2") (pinfunction "2_2") (pintype "passive"))
      (node (ref "C51") (pin "2") (pinfunction "2_2") (pintype "passive"))
      (node (ref "C52") (pin "2") (pinfunction "2_2") (pintype "passive"))
      (node (ref "C55") (pin "2") (pinfunction "2_2") (pintype "passive"))
      (node (ref "C56") (pin "2") (pinfunction "2_2") (pintype "passive"))
      (node (ref "C80") (pin "1") (pinfunction "1_1") (pintype "passive"))
      (node (ref "IC24") (pin "6") (pinfunction "VO2_6") (pintype "input"))
      (node (ref "L3") (pin "2") (pinfunction "2_2") (pintype "passive"))
      (node (ref "R125") (pin "2") (pinfunction "2_2") (pintype "passive"))
      (node (ref "R23") (pin "1") (pinfunction "1_1") (pintype "passive"))
    )
    (net (code "85") (name "P3V3") (class "Default")
      (node (ref "B8") (pin "1") (pinfunction "1_1") (pintype "bidirectional"))
      (node (ref "C119") (pin "2") (pinfunction "2_2") (pintype "passive"))
      (node (ref "C135") (pin "2") (pinfunction "2_2") (pintype "passive"))
      (node (ref "C136") (pin "2") (pinfunction "2_2") (pintype "passive"))
      (node (ref "C137") (pin "2") (pinfunction "2_2") (pintype "passive"))
      (node (ref "C138") (pin "2") (pinfunction "2_2") (pintype "passive"))
      (node (ref "C44") (pin "1") (pinfunction "1_1") (pintype "passive"))
      (node (ref "C61") (pin "2") (pinfunction "2_2") (pintype "passive"))
      (node (ref "IC23") (pin "3") (pinfunction "VDD_3") (pintype "power_in"))
      (node (ref "IC8") (pin "10") (pinfunction "VIN_10") (pintype "power_in"))
      (node (ref "IC8") (pin "7") (pinfunction "EN_7") (pintype "input"))
      (node (ref "IC9") (pin "1") (pinfunction "VO1_1") (pintype "input"))
      (node (ref "L16") (pin "2") (pinfunction "2_2") (pintype "passive"))
      (node (ref "R106") (pin "2") (pinfunction "2_2") (pintype "passive"))
      (node (ref "R111") (pin "2") (pinfunction "2_2") (pintype "passive"))
      (node (ref "R112") (pin "2") (pinfunction "2_2") (pintype "passive"))
      (node (ref "R118") (pin "2") (pinfunction "2_2") (pintype "passive"))
      (node (ref "R134") (pin "2") (pinfunction "2_2") (pintype "passive"))
      (node (ref "R150") (pin "2") (pinfunction "2_2") (pintype "passive"))
    )
    (net (code "86") (name "P3V3_FMC1") (class "Default")
      (node (ref "C176") (pin "2") (pinfunction "2_2") (pintype "passive"))
      (node (ref "C179") (pin "2") (pinfunction "2_2") (pintype "passive"))
      (node (ref "C180") (pin "2") (pinfunction "2_2") (pintype "passive"))
      (node (ref "C181") (pin "2") (pinfunction "2_2") (pintype "passive"))
      (node (ref "C182") (pin "2") (pinfunction "2_2") (pintype "passive"))
      (node (ref "C87") (pin "1") (pinfunction "1_1") (pintype "passive"))
      (node (ref "IC11") (pin "1") (pinfunction "VO1_1") (pintype "input"))
      (node (ref "L4") (pin "2") (pinfunction "2_2") (pintype "passive"))
      (node (ref "R1") (pin "2") (pinfunction "2_2") (pintype "passive"))
      (node (ref "R113") (pin "2") (pinfunction "2_2") (pintype "passive"))
    )
    (net (code "87") (name "P3V3_FMC2") (class "Default")
      (node (ref "C208") (pin "2") (pinfunction "2_2") (pintype "passive"))
      (node (ref "C81") (pin "2") (pinfunction "2_2") (pintype "passive"))
      (node (ref "C83") (pin "2") (pinfunction "2_2") (pintype "passive"))
      (node (ref "C85") (pin "2") (pinfunction "2_2") (pintype "passive"))
      (node (ref "C86") (pin "2") (pinfunction "2_2") (pintype "passive"))
      (node (ref "C88") (pin "1") (pinfunction "1_1") (pintype "passive"))
      (node (ref "IC11") (pin "6") (pinfunction "VO2_6") (pintype "input"))
      (node (ref "L12") (pin "2") (pinfunction "2_2") (pintype "passive"))
      (node (ref "R116") (pin "2") (pinfunction "2_2") (pintype "passive"))
      (node (ref "R5") (pin "2") (pinfunction "2_2") (pintype "passive"))
    )
    (net (code "88") (name "P12V") (class "Default")
      (node (ref "B5") (pin "1") (pinfunction "1_1") (pintype "bidirectional"))
      (node (ref "C1") (pin "1") (pinfunction "1_1") (pintype "passive"))
      (node (ref "C175") (pin "1") (pinfunction "1_1") (pintype "passive"))
      (node (ref "C31") (pin "2") (pinfunction "2_2") (pintype "passive"))
      (node (ref "C37") (pin "1") (pinfunction "1_1") (pintype "passive"))
      (node (ref "C413") (pin "1") (pinfunction "1_1") (pintype "passive"))
      (node (ref "C427") (pin "1") (pinfunction "1_1") (pintype "passive"))
      (node (ref "C428") (pin "1") (pinfunction "1_1") (pintype "passive"))
      (node (ref "C429") (pin "1") (pinfunction "1_1") (pintype "passive"))
      (node (ref "C430") (pin "1") (pinfunction "1_1") (pintype "passive"))
      (node (ref "C431") (pin "1") (pinfunction "1_1") (pintype "passive"))
      (node (ref "C432") (pin "1") (pinfunction "1_1") (pintype "passive"))
      (node (ref "C433") (pin "1") (pinfunction "1_1") (pintype "passive"))
      (node (ref "C434") (pin "1") (pinfunction "1_1") (pintype "passive"))
      (node (ref "C435") (pin "1") (pinfunction "1_1") (pintype "passive"))
      (node (ref "C438") (pin "1") (pinfunction "1_1") (pintype "passive"))
      (node (ref "C439") (pin "1") (pinfunction "1_1") (pintype "passive"))
      (node (ref "C440") (pin "1") (pinfunction "1_1") (pintype "passive"))
      (node (ref "C67") (pin "1") (pinfunction "1_1") (pintype "passive"))
      (node (ref "C70") (pin "1") (pinfunction "1_1") (pintype "passive"))
      (node (ref "C71") (pin "1") (pinfunction "1_1") (pintype "passive"))
      (node (ref "C82") (pin "1") (pinfunction "1_1") (pintype "passive"))
      (node (ref "C91") (pin "1") (pinfunction "1_1") (pintype "passive"))
      (node (ref "D1") (pin "1") (pinfunction "C_1") (pintype "passive"))
      (node (ref "F2") (pin "2") (pinfunction "2_2") (pintype "passive"))
      (node (ref "IC11") (pin "17") (pinfunction "VIN_17") (pintype "input"))
      (node (ref "IC2") (pin "17") (pinfunction "VIN_17") (pintype "input"))
      (node (ref "LD6") (pin "2") (pinfunction "A_2") (pintype "passive"))
      (node (ref "R60") (pin "2") (pinfunction "2_2") (pintype "passive"))
      (node (ref "T1") (pin "5") (pinfunction "D_5") (pintype "passive"))
      (node (ref "T1") (pin "6") (pinfunction "D_6") (pintype "passive"))
      (node (ref "T11") (pin "5") (pinfunction "D_5") (pintype "passive"))
      (node (ref "T11") (pin "6") (pinfunction "D_6") (pintype "passive"))
      (node (ref "T2") (pin "5") (pinfunction "D_5") (pintype "passive"))
      (node (ref "T2") (pin "6") (pinfunction "D_6") (pintype "passive"))
      (node (ref "T3") (pin "5") (pinfunction "D_5") (pintype "passive"))
      (node (ref "T3") (pin "6") (pinfunction "D_6") (pintype "passive"))
      (node (ref "T4") (pin "5") (pinfunction "D_5") (pintype "passive"))
      (node (ref "T4") (pin "6") (pinfunction "D_6") (pintype "passive"))
      (node (ref "T7") (pin "5") (pinfunction "D_5") (pintype "passive"))
      (node (ref "T7") (pin "6") (pinfunction "D_6") (pintype "passive"))
      (node (ref "T8") (pin "5") (pinfunction "D_5") (pintype "passive"))
      (node (ref "T8") (pin "6") (pinfunction "D_6") (pintype "passive"))
      (node (ref "T9") (pin "5") (pinfunction "D_5") (pintype "passive"))
      (node (ref "T9") (pin "6") (pinfunction "D_6") (pintype "passive"))
    )
    (net (code "89") (name "P12V_FMC1") (class "Default")
      (node (ref "C24") (pin "1") (pinfunction "1_1") (pintype "passive"))
      (node (ref "C241") (pin "1") (pinfunction "1_1") (pintype "passive"))
      (node (ref "F1") (pin "2") (pinfunction "2_2") (pintype "passive"))
      (node (ref "R108") (pin "2") (pinfunction "2_2") (pintype "passive"))
    )
    (net (code "90") (name "P12V_FMC2") (class "Default")
      (node (ref "C41") (pin "1") (pinfunction "1_1") (pintype "passive"))
      (node (ref "C412") (pin "1") (pinfunction "1_1") (pintype "passive"))
      (node (ref "F3") (pin "2") (pinfunction "2_2") (pintype "passive"))
      (node (ref "R124") (pin "2") (pinfunction "2_2") (pintype "passive"))
    )
    (net (code "91") (name "V12P0VME") (class "Default")
      (node (ref "C218") (pin "2") (pinfunction "2_2") (pintype "passive"))
      (node (ref "C30") (pin "1") (pinfunction "1_1") (pintype "passive"))
      (node (ref "F1") (pin "1") (pinfunction "1_1") (pintype "passive"))
      (node (ref "F2") (pin "1") (pinfunction "1_1") (pintype "passive"))
      (node (ref "F3") (pin "1") (pinfunction "1_1") (pintype "passive"))
      (node (ref "IC24") (pin "17") (pinfunction "VIN_17") (pintype "input"))
      (node (ref "IC9") (pin "17") (pinfunction "VIN_17") (pintype "input"))
      (node (ref "J1") (pin "1") (pinfunction "1_1") (pintype "bidirectional"))
    )
    (net (code "92") (name "VREF_DDR3") (class "Default")
      (node (ref "C68") (pin "2") (pinfunction "2_2") (pintype "passive"))
      (node (ref "IC8") (pin "6") (pinfunction "REFOUT_6") (pintype "output"))
    )
    (net (code "93") (name "VTT_DDR3") (class "Default")
      (node (ref "C62") (pin "2") (pinfunction "2_2") (pintype "passive"))
      (node (ref "C65") (pin "2") (pinfunction "2_2") (pintype "passive"))
      (node (ref "IC8") (pin "3") (pinfunction "VO_3") (pintype "power_in"))
      (node (ref "IC8") (pin "5") (pinfunction "VOSNS_5") (pintype "input"))
    )
    (net (code "94") (name "unconnected-(J1-Pad4)") (class "Default")
      (node (ref "J1") (pin "4") (pinfunction "4_4") (pintype "bidirectional"))
    )
  )
)
